# 2_RGB_s_knees.net
KiCad netlist of a schematic drawn in Altium Designer
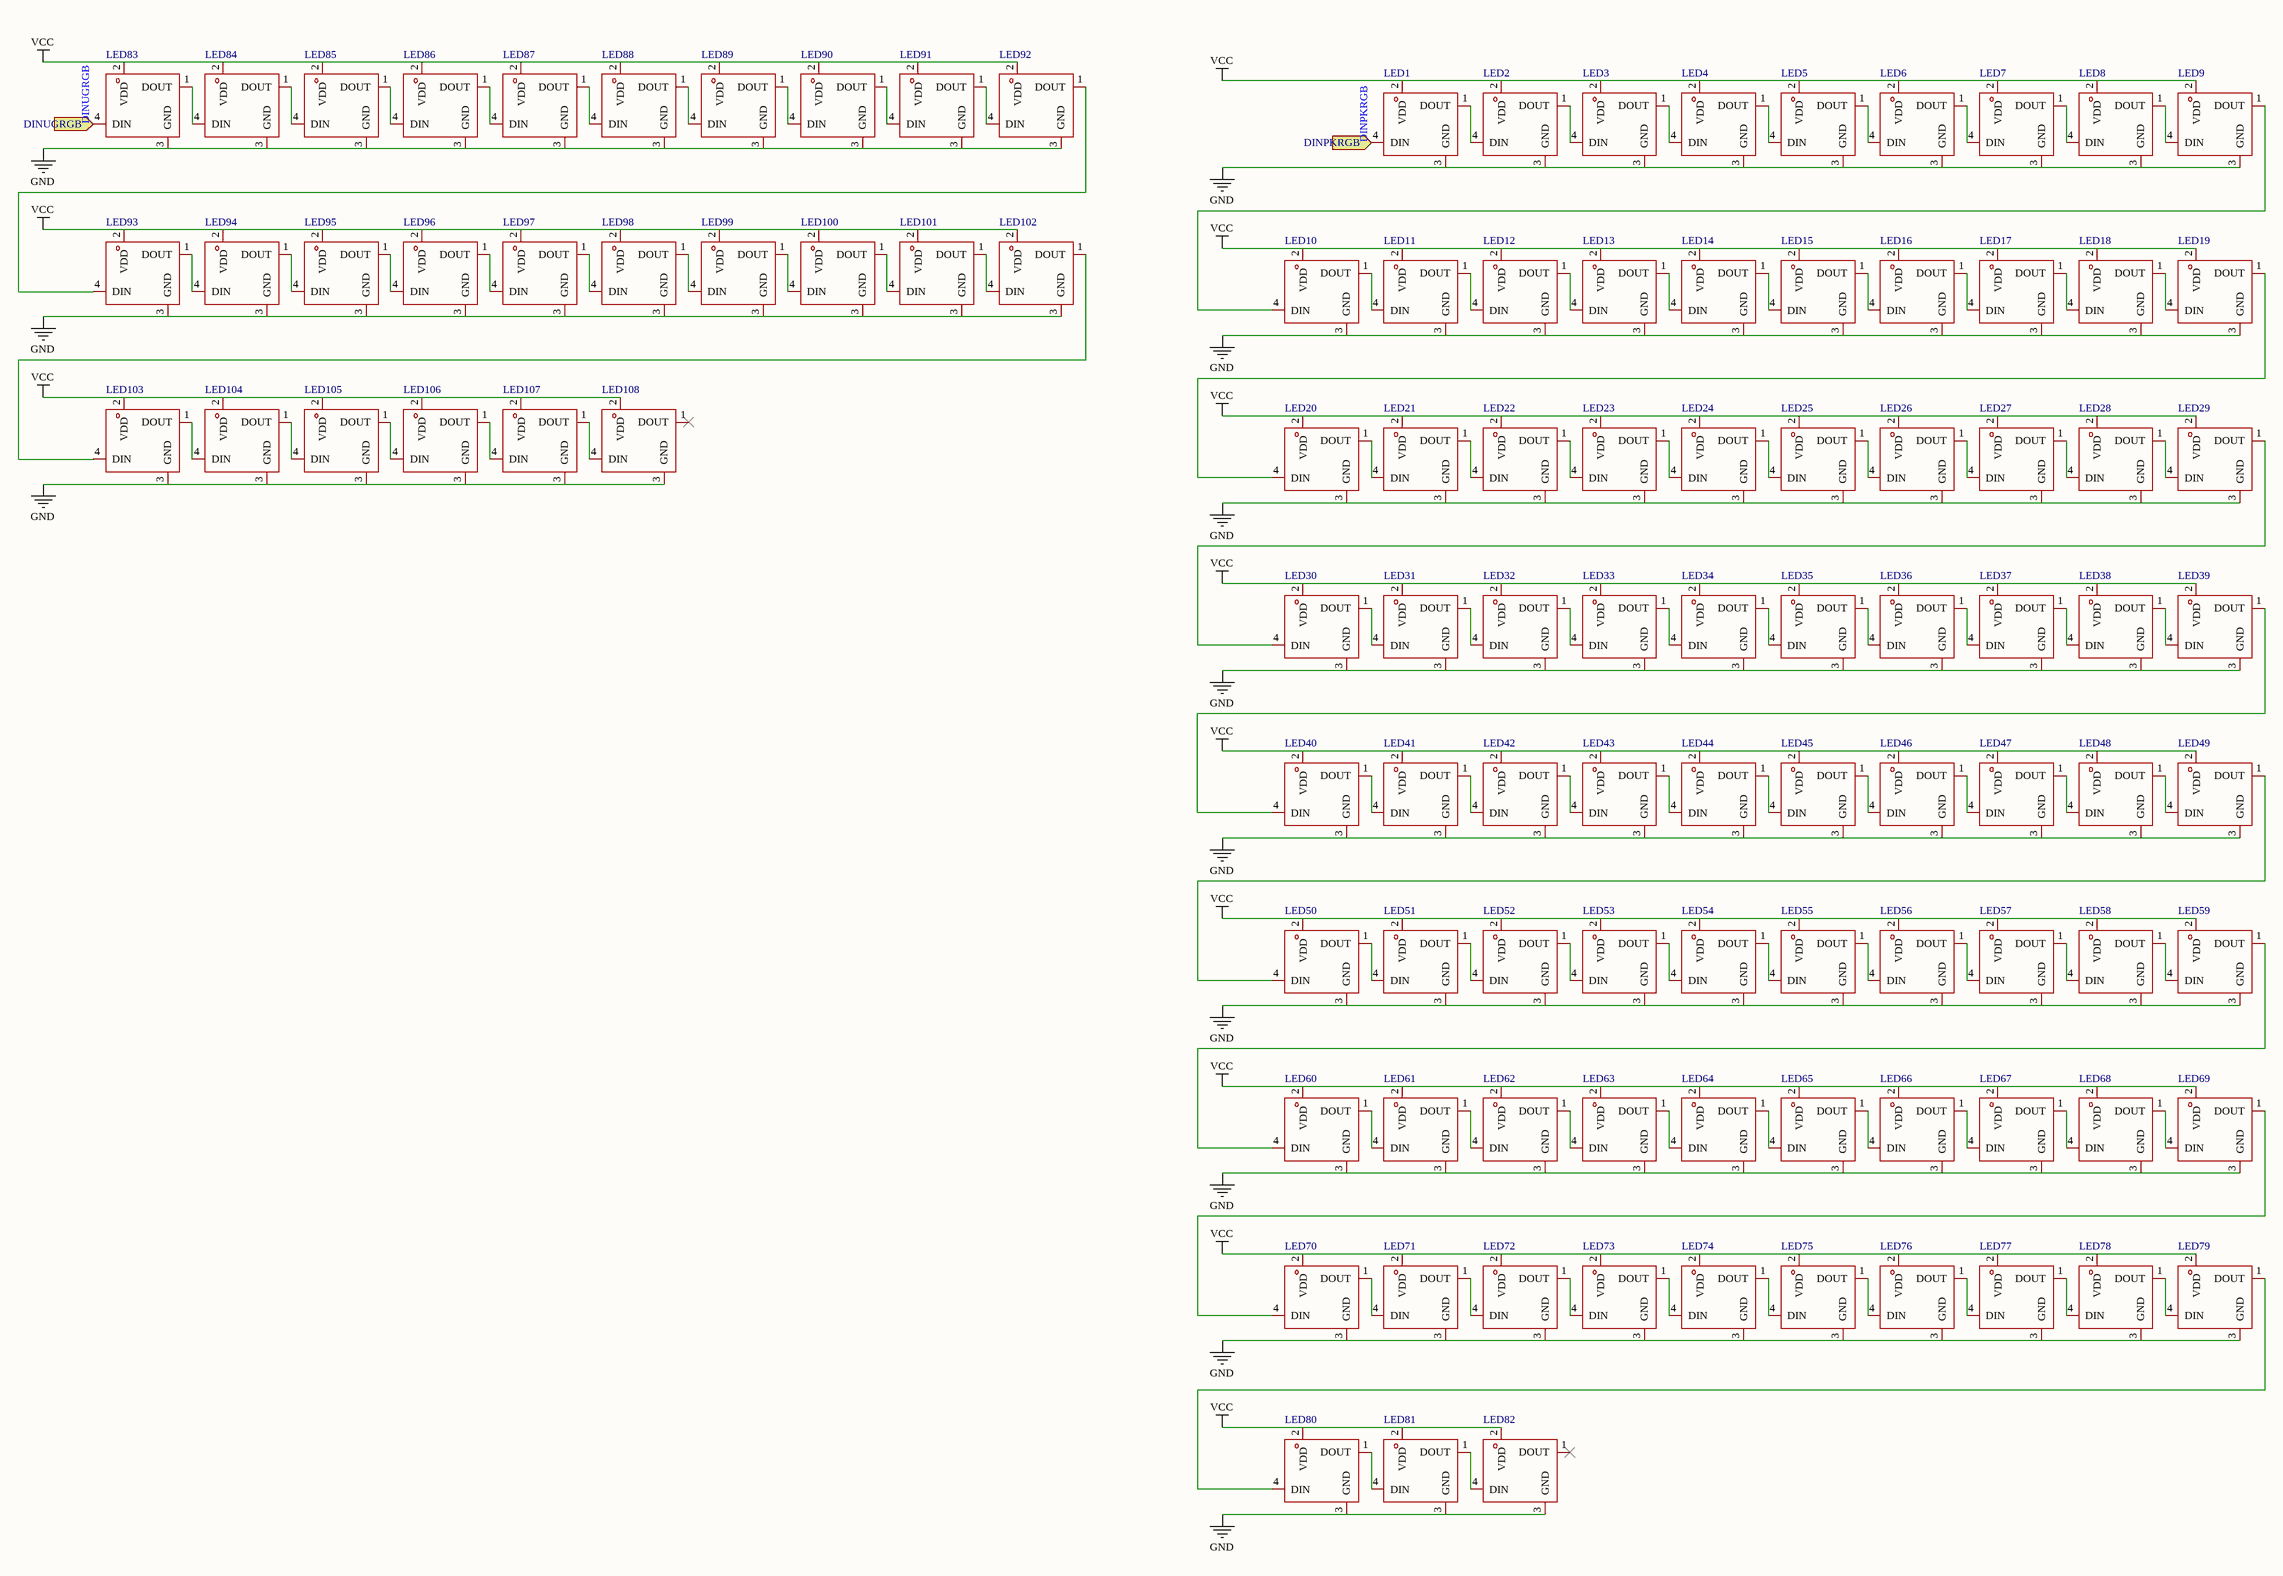
[diagram p0: 2_RGB's knees.schdoc]

(export (version "E")
  (design (tool "Eeschema 10.0.6"))
  (components
    (comp (ref "LED1")
      (value "XL-1010RGBC-WS2812B")
      (footprint "LED-SMD_4P-L1.0-W1.0-TL_XL-1010RGBC-WS2812B")
      (fields (field (name "MANUFACTURER") "XINGLIGHT(成兴光)"))
      (libsource (lib "altium-import") (part "root_0_XL-1010RGBC-WS2812B_"))
    )
    (comp (ref "LED2")
      (value "XL-1010RGBC-WS2812B")
      (footprint "LED-SMD_4P-L1.0-W1.0-TL_XL-1010RGBC-WS2812B")
      (fields (field (name "MANUFACTURER") "XINGLIGHT(成兴光)"))
      (libsource (lib "altium-import") (part "root_0_XL-1010RGBC-WS2812B_"))
    )
    (comp (ref "LED3")
      (value "XL-1010RGBC-WS2812B")
      (footprint "LED-SMD_4P-L1.0-W1.0-TL_XL-1010RGBC-WS2812B")
      (fields (field (name "MANUFACTURER") "XINGLIGHT(成兴光)"))
      (libsource (lib "altium-import") (part "root_0_XL-1010RGBC-WS2812B_"))
    )
    (comp (ref "LED4")
      (value "XL-1010RGBC-WS2812B")
      (footprint "LED-SMD_4P-L1.0-W1.0-TL_XL-1010RGBC-WS2812B")
      (fields (field (name "MANUFACTURER") "XINGLIGHT(成兴光)"))
      (libsource (lib "altium-import") (part "root_0_XL-1010RGBC-WS2812B_"))
    )
    (comp (ref "LED5")
      (value "XL-1010RGBC-WS2812B")
      (footprint "LED-SMD_4P-L1.0-W1.0-TL_XL-1010RGBC-WS2812B")
      (fields (field (name "MANUFACTURER") "XINGLIGHT(成兴光)"))
      (libsource (lib "altium-import") (part "root_0_XL-1010RGBC-WS2812B_"))
    )
    (comp (ref "LED6")
      (value "XL-1010RGBC-WS2812B")
      (footprint "LED-SMD_4P-L1.0-W1.0-TL_XL-1010RGBC-WS2812B")
      (fields (field (name "MANUFACTURER") "XINGLIGHT(成兴光)"))
      (libsource (lib "altium-import") (part "root_0_XL-1010RGBC-WS2812B_"))
    )
    (comp (ref "LED7")
      (value "XL-1010RGBC-WS2812B")
      (footprint "LED-SMD_4P-L1.0-W1.0-TL_XL-1010RGBC-WS2812B")
      (fields (field (name "MANUFACTURER") "XINGLIGHT(成兴光)"))
      (libsource (lib "altium-import") (part "root_0_XL-1010RGBC-WS2812B_"))
    )
    (comp (ref "LED8")
      (value "XL-1010RGBC-WS2812B")
      (footprint "LED-SMD_4P-L1.0-W1.0-TL_XL-1010RGBC-WS2812B")
      (fields (field (name "MANUFACTURER") "XINGLIGHT(成兴光)"))
      (libsource (lib "altium-import") (part "root_0_XL-1010RGBC-WS2812B_"))
    )
    (comp (ref "LED9")
      (value "XL-1010RGBC-WS2812B")
      (footprint "LED-SMD_4P-L1.0-W1.0-TL_XL-1010RGBC-WS2812B")
      (fields (field (name "MANUFACTURER") "XINGLIGHT(成兴光)"))
      (libsource (lib "altium-import") (part "root_0_XL-1010RGBC-WS2812B_"))
    )
    (comp (ref "LED10")
      (value "XL-1010RGBC-WS2812B")
      (footprint "LED-SMD_4P-L1.0-W1.0-TL_XL-1010RGBC-WS2812B")
      (fields (field (name "MANUFACTURER") "XINGLIGHT(成兴光)"))
      (libsource (lib "altium-import") (part "root_0_XL-1010RGBC-WS2812B_"))
    )
    (comp (ref "LED11")
      (value "XL-1010RGBC-WS2812B")
      (footprint "LED-SMD_4P-L1.0-W1.0-TL_XL-1010RGBC-WS2812B")
      (fields (field (name "MANUFACTURER") "XINGLIGHT(成兴光)"))
      (libsource (lib "altium-import") (part "root_0_XL-1010RGBC-WS2812B_"))
    )
    (comp (ref "LED12")
      (value "XL-1010RGBC-WS2812B")
      (footprint "LED-SMD_4P-L1.0-W1.0-TL_XL-1010RGBC-WS2812B")
      (fields (field (name "MANUFACTURER") "XINGLIGHT(成兴光)"))
      (libsource (lib "altium-import") (part "root_0_XL-1010RGBC-WS2812B_"))
    )
    (comp (ref "LED13")
      (value "XL-1010RGBC-WS2812B")
      (footprint "LED-SMD_4P-L1.0-W1.0-TL_XL-1010RGBC-WS2812B")
      (fields (field (name "MANUFACTURER") "XINGLIGHT(成兴光)"))
      (libsource (lib "altium-import") (part "root_0_XL-1010RGBC-WS2812B_"))
    )
    (comp (ref "LED14")
      (value "XL-1010RGBC-WS2812B")
      (footprint "LED-SMD_4P-L1.0-W1.0-TL_XL-1010RGBC-WS2812B")
      (fields (field (name "MANUFACTURER") "XINGLIGHT(成兴光)"))
      (libsource (lib "altium-import") (part "root_0_XL-1010RGBC-WS2812B_"))
    )
    (comp (ref "LED15")
      (value "XL-1010RGBC-WS2812B")
      (footprint "LED-SMD_4P-L1.0-W1.0-TL_XL-1010RGBC-WS2812B")
      (fields (field (name "MANUFACTURER") "XINGLIGHT(成兴光)"))
      (libsource (lib "altium-import") (part "root_0_XL-1010RGBC-WS2812B_"))
    )
    (comp (ref "LED16")
      (value "XL-1010RGBC-WS2812B")
      (footprint "LED-SMD_4P-L1.0-W1.0-TL_XL-1010RGBC-WS2812B")
      (fields (field (name "MANUFACTURER") "XINGLIGHT(成兴光)"))
      (libsource (lib "altium-import") (part "root_0_XL-1010RGBC-WS2812B_"))
    )
    (comp (ref "LED17")
      (value "XL-1010RGBC-WS2812B")
      (footprint "LED-SMD_4P-L1.0-W1.0-TL_XL-1010RGBC-WS2812B")
      (fields (field (name "MANUFACTURER") "XINGLIGHT(成兴光)"))
      (libsource (lib "altium-import") (part "root_0_XL-1010RGBC-WS2812B_"))
    )
    (comp (ref "LED18")
      (value "XL-1010RGBC-WS2812B")
      (footprint "LED-SMD_4P-L1.0-W1.0-TL_XL-1010RGBC-WS2812B")
      (fields (field (name "MANUFACTURER") "XINGLIGHT(成兴光)"))
      (libsource (lib "altium-import") (part "root_0_XL-1010RGBC-WS2812B_"))
    )
    (comp (ref "LED19")
      (value "XL-1010RGBC-WS2812B")
      (footprint "LED-SMD_4P-L1.0-W1.0-TL_XL-1010RGBC-WS2812B")
      (fields (field (name "MANUFACTURER") "XINGLIGHT(成兴光)"))
      (libsource (lib "altium-import") (part "root_0_XL-1010RGBC-WS2812B_"))
    )
    (comp (ref "LED20")
      (value "XL-1010RGBC-WS2812B")
      (footprint "LED-SMD_4P-L1.0-W1.0-TL_XL-1010RGBC-WS2812B")
      (fields (field (name "MANUFACTURER") "XINGLIGHT(成兴光)"))
      (libsource (lib "altium-import") (part "root_0_XL-1010RGBC-WS2812B_"))
    )
    (comp (ref "LED21")
      (value "XL-1010RGBC-WS2812B")
      (footprint "LED-SMD_4P-L1.0-W1.0-TL_XL-1010RGBC-WS2812B")
      (fields (field (name "MANUFACTURER") "XINGLIGHT(成兴光)"))
      (libsource (lib "altium-import") (part "root_0_XL-1010RGBC-WS2812B_"))
    )
    (comp (ref "LED22")
      (value "XL-1010RGBC-WS2812B")
      (footprint "LED-SMD_4P-L1.0-W1.0-TL_XL-1010RGBC-WS2812B")
      (fields (field (name "MANUFACTURER") "XINGLIGHT(成兴光)"))
      (libsource (lib "altium-import") (part "root_0_XL-1010RGBC-WS2812B_"))
    )
    (comp (ref "LED23")
      (value "XL-1010RGBC-WS2812B")
      (footprint "LED-SMD_4P-L1.0-W1.0-TL_XL-1010RGBC-WS2812B")
      (fields (field (name "MANUFACTURER") "XINGLIGHT(成兴光)"))
      (libsource (lib "altium-import") (part "root_0_XL-1010RGBC-WS2812B_"))
    )
    (comp (ref "LED24")
      (value "XL-1010RGBC-WS2812B")
      (footprint "LED-SMD_4P-L1.0-W1.0-TL_XL-1010RGBC-WS2812B")
      (fields (field (name "MANUFACTURER") "XINGLIGHT(成兴光)"))
      (libsource (lib "altium-import") (part "root_0_XL-1010RGBC-WS2812B_"))
    )
    (comp (ref "LED25")
      (value "XL-1010RGBC-WS2812B")
      (footprint "LED-SMD_4P-L1.0-W1.0-TL_XL-1010RGBC-WS2812B")
      (fields (field (name "MANUFACTURER") "XINGLIGHT(成兴光)"))
      (libsource (lib "altium-import") (part "root_0_XL-1010RGBC-WS2812B_"))
    )
    (comp (ref "LED26")
      (value "XL-1010RGBC-WS2812B")
      (footprint "LED-SMD_4P-L1.0-W1.0-TL_XL-1010RGBC-WS2812B")
      (fields (field (name "MANUFACTURER") "XINGLIGHT(成兴光)"))
      (libsource (lib "altium-import") (part "root_0_XL-1010RGBC-WS2812B_"))
    )
    (comp (ref "LED27")
      (value "XL-1010RGBC-WS2812B")
      (footprint "LED-SMD_4P-L1.0-W1.0-TL_XL-1010RGBC-WS2812B")
      (fields (field (name "MANUFACTURER") "XINGLIGHT(成兴光)"))
      (libsource (lib "altium-import") (part "root_0_XL-1010RGBC-WS2812B_"))
    )
    (comp (ref "LED28")
      (value "XL-1010RGBC-WS2812B")
      (footprint "LED-SMD_4P-L1.0-W1.0-TL_XL-1010RGBC-WS2812B")
      (fields (field (name "MANUFACTURER") "XINGLIGHT(成兴光)"))
      (libsource (lib "altium-import") (part "root_0_XL-1010RGBC-WS2812B_"))
    )
    (comp (ref "LED29")
      (value "XL-1010RGBC-WS2812B")
      (footprint "LED-SMD_4P-L1.0-W1.0-TL_XL-1010RGBC-WS2812B")
      (fields (field (name "MANUFACTURER") "XINGLIGHT(成兴光)"))
      (libsource (lib "altium-import") (part "root_0_XL-1010RGBC-WS2812B_"))
    )
    (comp (ref "LED30")
      (value "XL-1010RGBC-WS2812B")
      (footprint "LED-SMD_4P-L1.0-W1.0-TL_XL-1010RGBC-WS2812B")
      (fields (field (name "MANUFACTURER") "XINGLIGHT(成兴光)"))
      (libsource (lib "altium-import") (part "root_0_XL-1010RGBC-WS2812B_"))
    )
    (comp (ref "LED31")
      (value "XL-1010RGBC-WS2812B")
      (footprint "LED-SMD_4P-L1.0-W1.0-TL_XL-1010RGBC-WS2812B")
      (fields (field (name "MANUFACTURER") "XINGLIGHT(成兴光)"))
      (libsource (lib "altium-import") (part "root_0_XL-1010RGBC-WS2812B_"))
    )
    (comp (ref "LED32")
      (value "XL-1010RGBC-WS2812B")
      (footprint "LED-SMD_4P-L1.0-W1.0-TL_XL-1010RGBC-WS2812B")
      (fields (field (name "MANUFACTURER") "XINGLIGHT(成兴光)"))
      (libsource (lib "altium-import") (part "root_0_XL-1010RGBC-WS2812B_"))
    )
    (comp (ref "LED33")
      (value "XL-1010RGBC-WS2812B")
      (footprint "LED-SMD_4P-L1.0-W1.0-TL_XL-1010RGBC-WS2812B")
      (fields (field (name "MANUFACTURER") "XINGLIGHT(成兴光)"))
      (libsource (lib "altium-import") (part "root_0_XL-1010RGBC-WS2812B_"))
    )
    (comp (ref "LED34")
      (value "XL-1010RGBC-WS2812B")
      (footprint "LED-SMD_4P-L1.0-W1.0-TL_XL-1010RGBC-WS2812B")
      (fields (field (name "MANUFACTURER") "XINGLIGHT(成兴光)"))
      (libsource (lib "altium-import") (part "root_0_XL-1010RGBC-WS2812B_"))
    )
    (comp (ref "LED35")
      (value "XL-1010RGBC-WS2812B")
      (footprint "LED-SMD_4P-L1.0-W1.0-TL_XL-1010RGBC-WS2812B")
      (fields (field (name "MANUFACTURER") "XINGLIGHT(成兴光)"))
      (libsource (lib "altium-import") (part "root_0_XL-1010RGBC-WS2812B_"))
    )
    (comp (ref "LED36")
      (value "XL-1010RGBC-WS2812B")
      (footprint "LED-SMD_4P-L1.0-W1.0-TL_XL-1010RGBC-WS2812B")
      (fields (field (name "MANUFACTURER") "XINGLIGHT(成兴光)"))
      (libsource (lib "altium-import") (part "root_0_XL-1010RGBC-WS2812B_"))
    )
    (comp (ref "LED37")
      (value "XL-1010RGBC-WS2812B")
      (footprint "LED-SMD_4P-L1.0-W1.0-TL_XL-1010RGBC-WS2812B")
      (fields (field (name "MANUFACTURER") "XINGLIGHT(成兴光)"))
      (libsource (lib "altium-import") (part "root_0_XL-1010RGBC-WS2812B_"))
    )
    (comp (ref "LED38")
      (value "XL-1010RGBC-WS2812B")
      (footprint "LED-SMD_4P-L1.0-W1.0-TL_XL-1010RGBC-WS2812B")
      (fields (field (name "MANUFACTURER") "XINGLIGHT(成兴光)"))
      (libsource (lib "altium-import") (part "root_0_XL-1010RGBC-WS2812B_"))
    )
    (comp (ref "LED39")
      (value "XL-1010RGBC-WS2812B")
      (footprint "LED-SMD_4P-L1.0-W1.0-TL_XL-1010RGBC-WS2812B")
      (fields (field (name "MANUFACTURER") "XINGLIGHT(成兴光)"))
      (libsource (lib "altium-import") (part "root_0_XL-1010RGBC-WS2812B_"))
    )
    (comp (ref "LED40")
      (value "XL-1010RGBC-WS2812B")
      (footprint "LED-SMD_4P-L1.0-W1.0-TL_XL-1010RGBC-WS2812B")
      (fields (field (name "MANUFACTURER") "XINGLIGHT(成兴光)"))
      (libsource (lib "altium-import") (part "root_0_XL-1010RGBC-WS2812B_"))
    )
    (comp (ref "LED41")
      (value "XL-1010RGBC-WS2812B")
      (footprint "LED-SMD_4P-L1.0-W1.0-TL_XL-1010RGBC-WS2812B")
      (fields (field (name "MANUFACTURER") "XINGLIGHT(成兴光)"))
      (libsource (lib "altium-import") (part "root_0_XL-1010RGBC-WS2812B_"))
    )
    (comp (ref "LED42")
      (value "XL-1010RGBC-WS2812B")
      (footprint "LED-SMD_4P-L1.0-W1.0-TL_XL-1010RGBC-WS2812B")
      (fields (field (name "MANUFACTURER") "XINGLIGHT(成兴光)"))
      (libsource (lib "altium-import") (part "root_0_XL-1010RGBC-WS2812B_"))
    )
    (comp (ref "LED43")
      (value "XL-1010RGBC-WS2812B")
      (footprint "LED-SMD_4P-L1.0-W1.0-TL_XL-1010RGBC-WS2812B")
      (fields (field (name "MANUFACTURER") "XINGLIGHT(成兴光)"))
      (libsource (lib "altium-import") (part "root_0_XL-1010RGBC-WS2812B_"))
    )
    (comp (ref "LED44")
      (value "XL-1010RGBC-WS2812B")
      (footprint "LED-SMD_4P-L1.0-W1.0-TL_XL-1010RGBC-WS2812B")
      (fields (field (name "MANUFACTURER") "XINGLIGHT(成兴光)"))
      (libsource (lib "altium-import") (part "root_0_XL-1010RGBC-WS2812B_"))
    )
    (comp (ref "LED45")
      (value "XL-1010RGBC-WS2812B")
      (footprint "LED-SMD_4P-L1.0-W1.0-TL_XL-1010RGBC-WS2812B")
      (fields (field (name "MANUFACTURER") "XINGLIGHT(成兴光)"))
      (libsource (lib "altium-import") (part "root_0_XL-1010RGBC-WS2812B_"))
    )
    (comp (ref "LED46")
      (value "XL-1010RGBC-WS2812B")
      (footprint "LED-SMD_4P-L1.0-W1.0-TL_XL-1010RGBC-WS2812B")
      (fields (field (name "MANUFACTURER") "XINGLIGHT(成兴光)"))
      (libsource (lib "altium-import") (part "root_0_XL-1010RGBC-WS2812B_"))
    )
    (comp (ref "LED47")
      (value "XL-1010RGBC-WS2812B")
      (footprint "LED-SMD_4P-L1.0-W1.0-TL_XL-1010RGBC-WS2812B")
      (fields (field (name "MANUFACTURER") "XINGLIGHT(成兴光)"))
      (libsource (lib "altium-import") (part "root_0_XL-1010RGBC-WS2812B_"))
    )
    (comp (ref "LED48")
      (value "XL-1010RGBC-WS2812B")
      (footprint "LED-SMD_4P-L1.0-W1.0-TL_XL-1010RGBC-WS2812B")
      (fields (field (name "MANUFACTURER") "XINGLIGHT(成兴光)"))
      (libsource (lib "altium-import") (part "root_0_XL-1010RGBC-WS2812B_"))
    )
    (comp (ref "LED49")
      (value "XL-1010RGBC-WS2812B")
      (footprint "LED-SMD_4P-L1.0-W1.0-TL_XL-1010RGBC-WS2812B")
      (fields (field (name "MANUFACTURER") "XINGLIGHT(成兴光)"))
      (libsource (lib "altium-import") (part "root_0_XL-1010RGBC-WS2812B_"))
    )
    (comp (ref "LED50")
      (value "XL-1010RGBC-WS2812B")
      (footprint "LED-SMD_4P-L1.0-W1.0-TL_XL-1010RGBC-WS2812B")
      (fields (field (name "MANUFACTURER") "XINGLIGHT(成兴光)"))
      (libsource (lib "altium-import") (part "root_0_XL-1010RGBC-WS2812B_"))
    )
    (comp (ref "LED51")
      (value "XL-1010RGBC-WS2812B")
      (footprint "LED-SMD_4P-L1.0-W1.0-TL_XL-1010RGBC-WS2812B")
      (fields (field (name "MANUFACTURER") "XINGLIGHT(成兴光)"))
      (libsource (lib "altium-import") (part "root_0_XL-1010RGBC-WS2812B_"))
    )
    (comp (ref "LED52")
      (value "XL-1010RGBC-WS2812B")
      (footprint "LED-SMD_4P-L1.0-W1.0-TL_XL-1010RGBC-WS2812B")
      (fields (field (name "MANUFACTURER") "XINGLIGHT(成兴光)"))
      (libsource (lib "altium-import") (part "root_0_XL-1010RGBC-WS2812B_"))
    )
    (comp (ref "LED53")
      (value "XL-1010RGBC-WS2812B")
      (footprint "LED-SMD_4P-L1.0-W1.0-TL_XL-1010RGBC-WS2812B")
      (fields (field (name "MANUFACTURER") "XINGLIGHT(成兴光)"))
      (libsource (lib "altium-import") (part "root_0_XL-1010RGBC-WS2812B_"))
    )
    (comp (ref "LED54")
      (value "XL-1010RGBC-WS2812B")
      (footprint "LED-SMD_4P-L1.0-W1.0-TL_XL-1010RGBC-WS2812B")
      (fields (field (name "MANUFACTURER") "XINGLIGHT(成兴光)"))
      (libsource (lib "altium-import") (part "root_0_XL-1010RGBC-WS2812B_"))
    )
    (comp (ref "LED55")
      (value "XL-1010RGBC-WS2812B")
      (footprint "LED-SMD_4P-L1.0-W1.0-TL_XL-1010RGBC-WS2812B")
      (fields (field (name "MANUFACTURER") "XINGLIGHT(成兴光)"))
      (libsource (lib "altium-import") (part "root_0_XL-1010RGBC-WS2812B_"))
    )
    (comp (ref "LED56")
      (value "XL-1010RGBC-WS2812B")
      (footprint "LED-SMD_4P-L1.0-W1.0-TL_XL-1010RGBC-WS2812B")
      (fields (field (name "MANUFACTURER") "XINGLIGHT(成兴光)"))
      (libsource (lib "altium-import") (part "root_0_XL-1010RGBC-WS2812B_"))
    )
    (comp (ref "LED57")
      (value "XL-1010RGBC-WS2812B")
      (footprint "LED-SMD_4P-L1.0-W1.0-TL_XL-1010RGBC-WS2812B")
      (fields (field (name "MANUFACTURER") "XINGLIGHT(成兴光)"))
      (libsource (lib "altium-import") (part "root_0_XL-1010RGBC-WS2812B_"))
    )
    (comp (ref "LED58")
      (value "XL-1010RGBC-WS2812B")
      (footprint "LED-SMD_4P-L1.0-W1.0-TL_XL-1010RGBC-WS2812B")
      (fields (field (name "MANUFACTURER") "XINGLIGHT(成兴光)"))
      (libsource (lib "altium-import") (part "root_0_XL-1010RGBC-WS2812B_"))
    )
    (comp (ref "LED59")
      (value "XL-1010RGBC-WS2812B")
      (footprint "LED-SMD_4P-L1.0-W1.0-TL_XL-1010RGBC-WS2812B")
      (fields (field (name "MANUFACTURER") "XINGLIGHT(成兴光)"))
      (libsource (lib "altium-import") (part "root_0_XL-1010RGBC-WS2812B_"))
    )
    (comp (ref "LED60")
      (value "XL-1010RGBC-WS2812B")
      (footprint "LED-SMD_4P-L1.0-W1.0-TL_XL-1010RGBC-WS2812B")
      (fields (field (name "MANUFACTURER") "XINGLIGHT(成兴光)"))
      (libsource (lib "altium-import") (part "root_0_XL-1010RGBC-WS2812B_"))
    )
    (comp (ref "LED61")
      (value "XL-1010RGBC-WS2812B")
      (footprint "LED-SMD_4P-L1.0-W1.0-TL_XL-1010RGBC-WS2812B")
      (fields (field (name "MANUFACTURER") "XINGLIGHT(成兴光)"))
      (libsource (lib "altium-import") (part "root_0_XL-1010RGBC-WS2812B_"))
    )
    (comp (ref "LED62")
      (value "XL-1010RGBC-WS2812B")
      (footprint "LED-SMD_4P-L1.0-W1.0-TL_XL-1010RGBC-WS2812B")
      (fields (field (name "MANUFACTURER") "XINGLIGHT(成兴光)"))
      (libsource (lib "altium-import") (part "root_0_XL-1010RGBC-WS2812B_"))
    )
    (comp (ref "LED63")
      (value "XL-1010RGBC-WS2812B")
      (footprint "LED-SMD_4P-L1.0-W1.0-TL_XL-1010RGBC-WS2812B")
      (fields (field (name "MANUFACTURER") "XINGLIGHT(成兴光)"))
      (libsource (lib "altium-import") (part "root_0_XL-1010RGBC-WS2812B_"))
    )
    (comp (ref "LED64")
      (value "XL-1010RGBC-WS2812B")
      (footprint "LED-SMD_4P-L1.0-W1.0-TL_XL-1010RGBC-WS2812B")
      (fields (field (name "MANUFACTURER") "XINGLIGHT(成兴光)"))
      (libsource (lib "altium-import") (part "root_0_XL-1010RGBC-WS2812B_"))
    )
    (comp (ref "LED65")
      (value "XL-1010RGBC-WS2812B")
      (footprint "LED-SMD_4P-L1.0-W1.0-TL_XL-1010RGBC-WS2812B")
      (fields (field (name "MANUFACTURER") "XINGLIGHT(成兴光)"))
      (libsource (lib "altium-import") (part "root_0_XL-1010RGBC-WS2812B_"))
    )
    (comp (ref "LED66")
      (value "XL-1010RGBC-WS2812B")
      (footprint "LED-SMD_4P-L1.0-W1.0-TL_XL-1010RGBC-WS2812B")
      (fields (field (name "MANUFACTURER") "XINGLIGHT(成兴光)"))
      (libsource (lib "altium-import") (part "root_0_XL-1010RGBC-WS2812B_"))
    )
    (comp (ref "LED67")
      (value "XL-1010RGBC-WS2812B")
      (footprint "LED-SMD_4P-L1.0-W1.0-TL_XL-1010RGBC-WS2812B")
      (fields (field (name "MANUFACTURER") "XINGLIGHT(成兴光)"))
      (libsource (lib "altium-import") (part "root_0_XL-1010RGBC-WS2812B_"))
    )
    (comp (ref "LED68")
      (value "XL-1010RGBC-WS2812B")
      (footprint "LED-SMD_4P-L1.0-W1.0-TL_XL-1010RGBC-WS2812B")
      (fields (field (name "MANUFACTURER") "XINGLIGHT(成兴光)"))
      (libsource (lib "altium-import") (part "root_0_XL-1010RGBC-WS2812B_"))
    )
    (comp (ref "LED69")
      (value "XL-1010RGBC-WS2812B")
      (footprint "LED-SMD_4P-L1.0-W1.0-TL_XL-1010RGBC-WS2812B")
      (fields (field (name "MANUFACTURER") "XINGLIGHT(成兴光)"))
      (libsource (lib "altium-import") (part "root_0_XL-1010RGBC-WS2812B_"))
    )
    (comp (ref "LED70")
      (value "XL-1010RGBC-WS2812B")
      (footprint "LED-SMD_4P-L1.0-W1.0-TL_XL-1010RGBC-WS2812B")
      (fields (field (name "MANUFACTURER") "XINGLIGHT(成兴光)"))
      (libsource (lib "altium-import") (part "root_0_XL-1010RGBC-WS2812B_"))
    )
    (comp (ref "LED71")
      (value "XL-1010RGBC-WS2812B")
      (footprint "LED-SMD_4P-L1.0-W1.0-TL_XL-1010RGBC-WS2812B")
      (fields (field (name "MANUFACTURER") "XINGLIGHT(成兴光)"))
      (libsource (lib "altium-import") (part "root_0_XL-1010RGBC-WS2812B_"))
    )
    (comp (ref "LED72")
      (value "XL-1010RGBC-WS2812B")
      (footprint "LED-SMD_4P-L1.0-W1.0-TL_XL-1010RGBC-WS2812B")
      (fields (field (name "MANUFACTURER") "XINGLIGHT(成兴光)"))
      (libsource (lib "altium-import") (part "root_0_XL-1010RGBC-WS2812B_"))
    )
    (comp (ref "LED73")
      (value "XL-1010RGBC-WS2812B")
      (footprint "LED-SMD_4P-L1.0-W1.0-TL_XL-1010RGBC-WS2812B")
      (fields (field (name "MANUFACTURER") "XINGLIGHT(成兴光)"))
      (libsource (lib "altium-import") (part "root_0_XL-1010RGBC-WS2812B_"))
    )
    (comp (ref "LED74")
      (value "XL-1010RGBC-WS2812B")
      (footprint "LED-SMD_4P-L1.0-W1.0-TL_XL-1010RGBC-WS2812B")
      (fields (field (name "MANUFACTURER") "XINGLIGHT(成兴光)"))
      (libsource (lib "altium-import") (part "root_0_XL-1010RGBC-WS2812B_"))
    )
    (comp (ref "LED75")
      (value "XL-1010RGBC-WS2812B")
      (footprint "LED-SMD_4P-L1.0-W1.0-TL_XL-1010RGBC-WS2812B")
      (fields (field (name "MANUFACTURER") "XINGLIGHT(成兴光)"))
      (libsource (lib "altium-import") (part "root_0_XL-1010RGBC-WS2812B_"))
    )
    (comp (ref "LED76")
      (value "XL-1010RGBC-WS2812B")
      (footprint "LED-SMD_4P-L1.0-W1.0-TL_XL-1010RGBC-WS2812B")
      (fields (field (name "MANUFACTURER") "XINGLIGHT(成兴光)"))
      (libsource (lib "altium-import") (part "root_0_XL-1010RGBC-WS2812B_"))
    )
    (comp (ref "LED77")
      (value "XL-1010RGBC-WS2812B")
      (footprint "LED-SMD_4P-L1.0-W1.0-TL_XL-1010RGBC-WS2812B")
      (fields (field (name "MANUFACTURER") "XINGLIGHT(成兴光)"))
      (libsource (lib "altium-import") (part "root_0_XL-1010RGBC-WS2812B_"))
    )
    (comp (ref "LED78")
      (value "XL-1010RGBC-WS2812B")
      (footprint "LED-SMD_4P-L1.0-W1.0-TL_XL-1010RGBC-WS2812B")
      (fields (field (name "MANUFACTURER") "XINGLIGHT(成兴光)"))
      (libsource (lib "altium-import") (part "root_0_XL-1010RGBC-WS2812B_"))
    )
    (comp (ref "LED79")
      (value "XL-1010RGBC-WS2812B")
      (footprint "LED-SMD_4P-L1.0-W1.0-TL_XL-1010RGBC-WS2812B")
      (fields (field (name "MANUFACTURER") "XINGLIGHT(成兴光)"))
      (libsource (lib "altium-import") (part "root_0_XL-1010RGBC-WS2812B_"))
    )
    (comp (ref "LED80")
      (value "XL-1010RGBC-WS2812B")
      (footprint "LED-SMD_4P-L1.0-W1.0-TL_XL-1010RGBC-WS2812B")
      (fields (field (name "MANUFACTURER") "XINGLIGHT(成兴光)"))
      (libsource (lib "altium-import") (part "root_0_XL-1010RGBC-WS2812B_"))
    )
    (comp (ref "LED81")
      (value "XL-1010RGBC-WS2812B")
      (footprint "LED-SMD_4P-L1.0-W1.0-TL_XL-1010RGBC-WS2812B")
      (fields (field (name "MANUFACTURER") "XINGLIGHT(成兴光)"))
      (libsource (lib "altium-import") (part "root_0_XL-1010RGBC-WS2812B_"))
    )
    (comp (ref "LED82")
      (value "XL-1010RGBC-WS2812B")
      (footprint "LED-SMD_4P-L1.0-W1.0-TL_XL-1010RGBC-WS2812B")
      (fields (field (name "MANUFACTURER") "XINGLIGHT(成兴光)"))
      (libsource (lib "altium-import") (part "root_0_XL-1010RGBC-WS2812B_"))
    )
    (comp (ref "LED83")
      (value "XL-1010RGBC-WS2812B")
      (footprint "LED-SMD_4P-L1.0-W1.0-TL_XL-1010RGBC-WS2812B")
      (fields (field (name "MANUFACTURER") "XINGLIGHT(成兴光)"))
      (libsource (lib "altium-import") (part "root_0_XL-1010RGBC-WS2812B_"))
    )
    (comp (ref "LED84")
      (value "XL-1010RGBC-WS2812B")
      (footprint "LED-SMD_4P-L1.0-W1.0-TL_XL-1010RGBC-WS2812B")
      (fields (field (name "MANUFACTURER") "XINGLIGHT(成兴光)"))
      (libsource (lib "altium-import") (part "root_0_XL-1010RGBC-WS2812B_"))
    )
    (comp (ref "LED85")
      (value "XL-1010RGBC-WS2812B")
      (footprint "LED-SMD_4P-L1.0-W1.0-TL_XL-1010RGBC-WS2812B")
      (fields (field (name "MANUFACTURER") "XINGLIGHT(成兴光)"))
      (libsource (lib "altium-import") (part "root_0_XL-1010RGBC-WS2812B_"))
    )
    (comp (ref "LED86")
      (value "XL-1010RGBC-WS2812B")
      (footprint "LED-SMD_4P-L1.0-W1.0-TL_XL-1010RGBC-WS2812B")
      (fields (field (name "MANUFACTURER") "XINGLIGHT(成兴光)"))
      (libsource (lib "altium-import") (part "root_0_XL-1010RGBC-WS2812B_"))
    )
    (comp (ref "LED87")
      (value "XL-1010RGBC-WS2812B")
      (footprint "LED-SMD_4P-L1.0-W1.0-TL_XL-1010RGBC-WS2812B")
      (fields (field (name "MANUFACTURER") "XINGLIGHT(成兴光)"))
      (libsource (lib "altium-import") (part "root_0_XL-1010RGBC-WS2812B_"))
    )
    (comp (ref "LED88")
      (value "XL-1010RGBC-WS2812B")
      (footprint "LED-SMD_4P-L1.0-W1.0-TL_XL-1010RGBC-WS2812B")
      (fields (field (name "MANUFACTURER") "XINGLIGHT(成兴光)"))
      (libsource (lib "altium-import") (part "root_0_XL-1010RGBC-WS2812B_"))
    )
    (comp (ref "LED89")
      (value "XL-1010RGBC-WS2812B")
      (footprint "LED-SMD_4P-L1.0-W1.0-TL_XL-1010RGBC-WS2812B")
      (fields (field (name "MANUFACTURER") "XINGLIGHT(成兴光)"))
      (libsource (lib "altium-import") (part "root_0_XL-1010RGBC-WS2812B_"))
    )
    (comp (ref "LED90")
      (value "XL-1010RGBC-WS2812B")
      (footprint "LED-SMD_4P-L1.0-W1.0-TL_XL-1010RGBC-WS2812B")
      (fields (field (name "MANUFACTURER") "XINGLIGHT(成兴光)"))
      (libsource (lib "altium-import") (part "root_0_XL-1010RGBC-WS2812B_"))
    )
    (comp (ref "LED91")
      (value "XL-1010RGBC-WS2812B")
      (footprint "LED-SMD_4P-L1.0-W1.0-TL_XL-1010RGBC-WS2812B")
      (fields (field (name "MANUFACTURER") "XINGLIGHT(成兴光)"))
      (libsource (lib "altium-import") (part "root_0_XL-1010RGBC-WS2812B_"))
    )
    (comp (ref "LED92")
      (value "XL-1010RGBC-WS2812B")
      (footprint "LED-SMD_4P-L1.0-W1.0-TL_XL-1010RGBC-WS2812B")
      (fields (field (name "MANUFACTURER") "XINGLIGHT(成兴光)"))
      (libsource (lib "altium-import") (part "root_0_XL-1010RGBC-WS2812B_"))
    )
    (comp (ref "LED93")
      (value "XL-1010RGBC-WS2812B")
      (footprint "LED-SMD_4P-L1.0-W1.0-TL_XL-1010RGBC-WS2812B")
      (fields (field (name "MANUFACTURER") "XINGLIGHT(成兴光)"))
      (libsource (lib "altium-import") (part "root_0_XL-1010RGBC-WS2812B_"))
    )
    (comp (ref "LED94")
      (value "XL-1010RGBC-WS2812B")
      (footprint "LED-SMD_4P-L1.0-W1.0-TL_XL-1010RGBC-WS2812B")
      (fields (field (name "MANUFACTURER") "XINGLIGHT(成兴光)"))
      (libsource (lib "altium-import") (part "root_0_XL-1010RGBC-WS2812B_"))
    )
    (comp (ref "LED95")
      (value "XL-1010RGBC-WS2812B")
      (footprint "LED-SMD_4P-L1.0-W1.0-TL_XL-1010RGBC-WS2812B")
      (fields (field (name "MANUFACTURER") "XINGLIGHT(成兴光)"))
      (libsource (lib "altium-import") (part "root_0_XL-1010RGBC-WS2812B_"))
    )
    (comp (ref "LED96")
      (value "XL-1010RGBC-WS2812B")
      (footprint "LED-SMD_4P-L1.0-W1.0-TL_XL-1010RGBC-WS2812B")
      (fields (field (name "MANUFACTURER") "XINGLIGHT(成兴光)"))
      (libsource (lib "altium-import") (part "root_0_XL-1010RGBC-WS2812B_"))
    )
    (comp (ref "LED97")
      (value "XL-1010RGBC-WS2812B")
      (footprint "LED-SMD_4P-L1.0-W1.0-TL_XL-1010RGBC-WS2812B")
      (fields (field (name "MANUFACTURER") "XINGLIGHT(成兴光)"))
      (libsource (lib "altium-import") (part "root_0_XL-1010RGBC-WS2812B_"))
    )
    (comp (ref "LED98")
      (value "XL-1010RGBC-WS2812B")
      (footprint "LED-SMD_4P-L1.0-W1.0-TL_XL-1010RGBC-WS2812B")
      (fields (field (name "MANUFACTURER") "XINGLIGHT(成兴光)"))
      (libsource (lib "altium-import") (part "root_0_XL-1010RGBC-WS2812B_"))
    )
    (comp (ref "LED99")
      (value "XL-1010RGBC-WS2812B")
      (footprint "LED-SMD_4P-L1.0-W1.0-TL_XL-1010RGBC-WS2812B")
      (fields (field (name "MANUFACTURER") "XINGLIGHT(成兴光)"))
      (libsource (lib "altium-import") (part "root_0_XL-1010RGBC-WS2812B_"))
    )
    (comp (ref "LED100")
      (value "XL-1010RGBC-WS2812B")
      (footprint "LED-SMD_4P-L1.0-W1.0-TL_XL-1010RGBC-WS2812B")
      (fields (field (name "MANUFACTURER") "XINGLIGHT(成兴光)"))
      (libsource (lib "altium-import") (part "root_0_XL-1010RGBC-WS2812B_"))
    )
    (comp (ref "LED101")
      (value "XL-1010RGBC-WS2812B")
      (footprint "LED-SMD_4P-L1.0-W1.0-TL_XL-1010RGBC-WS2812B")
      (fields (field (name "MANUFACTURER") "XINGLIGHT(成兴光)"))
      (libsource (lib "altium-import") (part "root_0_XL-1010RGBC-WS2812B_"))
    )
    (comp (ref "LED102")
      (value "XL-1010RGBC-WS2812B")
      (footprint "LED-SMD_4P-L1.0-W1.0-TL_XL-1010RGBC-WS2812B")
      (fields (field (name "MANUFACTURER") "XINGLIGHT(成兴光)"))
      (libsource (lib "altium-import") (part "root_0_XL-1010RGBC-WS2812B_"))
    )
    (comp (ref "LED103")
      (value "XL-1010RGBC-WS2812B")
      (footprint "LED-SMD_4P-L1.0-W1.0-TL_XL-1010RGBC-WS2812B")
      (fields (field (name "MANUFACTURER") "XINGLIGHT(成兴光)"))
      (libsource (lib "altium-import") (part "root_0_XL-1010RGBC-WS2812B_"))
    )
    (comp (ref "LED104")
      (value "XL-1010RGBC-WS2812B")
      (footprint "LED-SMD_4P-L1.0-W1.0-TL_XL-1010RGBC-WS2812B")
      (fields (field (name "MANUFACTURER") "XINGLIGHT(成兴光)"))
      (libsource (lib "altium-import") (part "root_0_XL-1010RGBC-WS2812B_"))
    )
    (comp (ref "LED105")
      (value "XL-1010RGBC-WS2812B")
      (footprint "LED-SMD_4P-L1.0-W1.0-TL_XL-1010RGBC-WS2812B")
      (fields (field (name "MANUFACTURER") "XINGLIGHT(成兴光)"))
      (libsource (lib "altium-import") (part "root_0_XL-1010RGBC-WS2812B_"))
    )
    (comp (ref "LED106")
      (value "XL-1010RGBC-WS2812B")
      (footprint "LED-SMD_4P-L1.0-W1.0-TL_XL-1010RGBC-WS2812B")
      (fields (field (name "MANUFACTURER") "XINGLIGHT(成兴光)"))
      (libsource (lib "altium-import") (part "root_0_XL-1010RGBC-WS2812B_"))
    )
    (comp (ref "LED107")
      (value "XL-1010RGBC-WS2812B")
      (footprint "LED-SMD_4P-L1.0-W1.0-TL_XL-1010RGBC-WS2812B")
      (fields (field (name "MANUFACTURER") "XINGLIGHT(成兴光)"))
      (libsource (lib "altium-import") (part "root_0_XL-1010RGBC-WS2812B_"))
    )
    (comp (ref "LED108")
      (value "XL-1010RGBC-WS2812B")
      (footprint "LED-SMD_4P-L1.0-W1.0-TL_XL-1010RGBC-WS2812B")
      (fields (field (name "MANUFACTURER") "XINGLIGHT(成兴光)"))
      (libsource (lib "altium-import") (part "root_0_XL-1010RGBC-WS2812B_"))
    )
  )
  (nets
    (net (code "1") (name "/DINPKRGB") (class "Default")
      (node (ref "LED1") (pin "4") (pinfunction "DIN_4") (pintype "passive"))
    )
    (net (code "2") (name "/DINUGRGB") (class "Default")
      (node (ref "LED83") (pin "4") (pinfunction "DIN_4") (pintype "passive"))
    )
    (net (code "3") (name "GND") (class "Default")
      (node (ref "LED1") (pin "3") (pinfunction "GND_3") (pintype "passive"))
      (node (ref "LED10") (pin "3") (pinfunction "GND_3") (pintype "passive"))
      (node (ref "LED100") (pin "3") (pinfunction "GND_3") (pintype "passive"))
      (node (ref "LED101") (pin "3") (pinfunction "GND_3") (pintype "passive"))
      (node (ref "LED102") (pin "3") (pinfunction "GND_3") (pintype "passive"))
      (node (ref "LED103") (pin "3") (pinfunction "GND_3") (pintype "passive"))
      (node (ref "LED104") (pin "3") (pinfunction "GND_3") (pintype "passive"))
      (node (ref "LED105") (pin "3") (pinfunction "GND_3") (pintype "passive"))
      (node (ref "LED106") (pin "3") (pinfunction "GND_3") (pintype "passive"))
      (node (ref "LED107") (pin "3") (pinfunction "GND_3") (pintype "passive"))
      (node (ref "LED108") (pin "3") (pinfunction "GND_3") (pintype "passive"))
      (node (ref "LED11") (pin "3") (pinfunction "GND_3") (pintype "passive"))
      (node (ref "LED12") (pin "3") (pinfunction "GND_3") (pintype "passive"))
      (node (ref "LED13") (pin "3") (pinfunction "GND_3") (pintype "passive"))
      (node (ref "LED14") (pin "3") (pinfunction "GND_3") (pintype "passive"))
      (node (ref "LED15") (pin "3") (pinfunction "GND_3") (pintype "passive"))
      (node (ref "LED16") (pin "3") (pinfunction "GND_3") (pintype "passive"))
      (node (ref "LED17") (pin "3") (pinfunction "GND_3") (pintype "passive"))
      (node (ref "LED18") (pin "3") (pinfunction "GND_3") (pintype "passive"))
      (node (ref "LED19") (pin "3") (pinfunction "GND_3") (pintype "passive"))
      (node (ref "LED2") (pin "3") (pinfunction "GND_3") (pintype "passive"))
      (node (ref "LED20") (pin "3") (pinfunction "GND_3") (pintype "passive"))
      (node (ref "LED21") (pin "3") (pinfunction "GND_3") (pintype "passive"))
      (node (ref "LED22") (pin "3") (pinfunction "GND_3") (pintype "passive"))
      (node (ref "LED23") (pin "3") (pinfunction "GND_3") (pintype "passive"))
      (node (ref "LED24") (pin "3") (pinfunction "GND_3") (pintype "passive"))
      (node (ref "LED25") (pin "3") (pinfunction "GND_3") (pintype "passive"))
      (node (ref "LED26") (pin "3") (pinfunction "GND_3") (pintype "passive"))
      (node (ref "LED27") (pin "3") (pinfunction "GND_3") (pintype "passive"))
      (node (ref "LED28") (pin "3") (pinfunction "GND_3") (pintype "passive"))
      (node (ref "LED29") (pin "3") (pinfunction "GND_3") (pintype "passive"))
      (node (ref "LED3") (pin "3") (pinfunction "GND_3") (pintype "passive"))
      (node (ref "LED30") (pin "3") (pinfunction "GND_3") (pintype "passive"))
      (node (ref "LED31") (pin "3") (pinfunction "GND_3") (pintype "passive"))
      (node (ref "LED32") (pin "3") (pinfunction "GND_3") (pintype "passive"))
      (node (ref "LED33") (pin "3") (pinfunction "GND_3") (pintype "passive"))
      (node (ref "LED34") (pin "3") (pinfunction "GND_3") (pintype "passive"))
      (node (ref "LED35") (pin "3") (pinfunction "GND_3") (pintype "passive"))
      (node (ref "LED36") (pin "3") (pinfunction "GND_3") (pintype "passive"))
      (node (ref "LED37") (pin "3") (pinfunction "GND_3") (pintype "passive"))
      (node (ref "LED38") (pin "3") (pinfunction "GND_3") (pintype "passive"))
      (node (ref "LED39") (pin "3") (pinfunction "GND_3") (pintype "passive"))
      (node (ref "LED4") (pin "3") (pinfunction "GND_3") (pintype "passive"))
      (node (ref "LED40") (pin "3") (pinfunction "GND_3") (pintype "passive"))
      (node (ref "LED41") (pin "3") (pinfunction "GND_3") (pintype "passive"))
      (node (ref "LED42") (pin "3") (pinfunction "GND_3") (pintype "passive"))
      (node (ref "LED43") (pin "3") (pinfunction "GND_3") (pintype "passive"))
      (node (ref "LED44") (pin "3") (pinfunction "GND_3") (pintype "passive"))
      (node (ref "LED45") (pin "3") (pinfunction "GND_3") (pintype "passive"))
      (node (ref "LED46") (pin "3") (pinfunction "GND_3") (pintype "passive"))
      (node (ref "LED47") (pin "3") (pinfunction "GND_3") (pintype "passive"))
      (node (ref "LED48") (pin "3") (pinfunction "GND_3") (pintype "passive"))
      (node (ref "LED49") (pin "3") (pinfunction "GND_3") (pintype "passive"))
      (node (ref "LED5") (pin "3") (pinfunction "GND_3") (pintype "passive"))
      (node (ref "LED50") (pin "3") (pinfunction "GND_3") (pintype "passive"))
      (node (ref "LED51") (pin "3") (pinfunction "GND_3") (pintype "passive"))
      (node (ref "LED52") (pin "3") (pinfunction "GND_3") (pintype "passive"))
      (node (ref "LED53") (pin "3") (pinfunction "GND_3") (pintype "passive"))
      (node (ref "LED54") (pin "3") (pinfunction "GND_3") (pintype "passive"))
      (node (ref "LED55") (pin "3") (pinfunction "GND_3") (pintype "passive"))
      (node (ref "LED56") (pin "3") (pinfunction "GND_3") (pintype "passive"))
      (node (ref "LED57") (pin "3") (pinfunction "GND_3") (pintype "passive"))
      (node (ref "LED58") (pin "3") (pinfunction "GND_3") (pintype "passive"))
      (node (ref "LED59") (pin "3") (pinfunction "GND_3") (pintype "passive"))
      (node (ref "LED6") (pin "3") (pinfunction "GND_3") (pintype "passive"))
      (node (ref "LED60") (pin "3") (pinfunction "GND_3") (pintype "passive"))
      (node (ref "LED61") (pin "3") (pinfunction "GND_3") (pintype "passive"))
      (node (ref "LED62") (pin "3") (pinfunction "GND_3") (pintype "passive"))
      (node (ref "LED63") (pin "3") (pinfunction "GND_3") (pintype "passive"))
      (node (ref "LED64") (pin "3") (pinfunction "GND_3") (pintype "passive"))
      (node (ref "LED65") (pin "3") (pinfunction "GND_3") (pintype "passive"))
      (node (ref "LED66") (pin "3") (pinfunction "GND_3") (pintype "passive"))
      (node (ref "LED67") (pin "3") (pinfunction "GND_3") (pintype "passive"))
      (node (ref "LED68") (pin "3") (pinfunction "GND_3") (pintype "passive"))
      (node (ref "LED69") (pin "3") (pinfunction "GND_3") (pintype "passive"))
      (node (ref "LED7") (pin "3") (pinfunction "GND_3") (pintype "passive"))
      (node (ref "LED70") (pin "3") (pinfunction "GND_3") (pintype "passive"))
      (node (ref "LED71") (pin "3") (pinfunction "GND_3") (pintype "passive"))
      (node (ref "LED72") (pin "3") (pinfunction "GND_3") (pintype "passive"))
      (node (ref "LED73") (pin "3") (pinfunction "GND_3") (pintype "passive"))
      (node (ref "LED74") (pin "3") (pinfunction "GND_3") (pintype "passive"))
      (node (ref "LED75") (pin "3") (pinfunction "GND_3") (pintype "passive"))
      (node (ref "LED76") (pin "3") (pinfunction "GND_3") (pintype "passive"))
      (node (ref "LED77") (pin "3") (pinfunction "GND_3") (pintype "passive"))
      (node (ref "LED78") (pin "3") (pinfunction "GND_3") (pintype "passive"))
      (node (ref "LED79") (pin "3") (pinfunction "GND_3") (pintype "passive"))
      (node (ref "LED8") (pin "3") (pinfunction "GND_3") (pintype "passive"))
      (node (ref "LED80") (pin "3") (pinfunction "GND_3") (pintype "passive"))
      (node (ref "LED81") (pin "3") (pinfunction "GND_3") (pintype "passive"))
      (node (ref "LED82") (pin "3") (pinfunction "GND_3") (pintype "passive"))
      (node (ref "LED83") (pin "3") (pinfunction "GND_3") (pintype "passive"))
      (node (ref "LED84") (pin "3") (pinfunction "GND_3") (pintype "passive"))
      (node (ref "LED85") (pin "3") (pinfunction "GND_3") (pintype "passive"))
      (node (ref "LED86") (pin "3") (pinfunction "GND_3") (pintype "passive"))
      (node (ref "LED87") (pin "3") (pinfunction "GND_3") (pintype "passive"))
      (node (ref "LED88") (pin "3") (pinfunction "GND_3") (pintype "passive"))
      (node (ref "LED89") (pin "3") (pinfunction "GND_3") (pintype "passive"))
      (node (ref "LED9") (pin "3") (pinfunction "GND_3") (pintype "passive"))
      (node (ref "LED90") (pin "3") (pinfunction "GND_3") (pintype "passive"))
      (node (ref "LED91") (pin "3") (pinfunction "GND_3") (pintype "passive"))
      (node (ref "LED92") (pin "3") (pinfunction "GND_3") (pintype "passive"))
      (node (ref "LED93") (pin "3") (pinfunction "GND_3") (pintype "passive"))
      (node (ref "LED94") (pin "3") (pinfunction "GND_3") (pintype "passive"))
      (node (ref "LED95") (pin "3") (pinfunction "GND_3") (pintype "passive"))
      (node (ref "LED96") (pin "3") (pinfunction "GND_3") (pintype "passive"))
      (node (ref "LED97") (pin "3") (pinfunction "GND_3") (pintype "passive"))
      (node (ref "LED98") (pin "3") (pinfunction "GND_3") (pintype "passive"))
      (node (ref "LED99") (pin "3") (pinfunction "GND_3") (pintype "passive"))
    )
    (net (code "4") (name "Net-(LED1-DOUT)") (class "Default")
      (node (ref "LED1") (pin "1") (pinfunction "DOUT_1") (pintype "passive"))
      (node (ref "LED2") (pin "4") (pinfunction "DIN_4") (pintype "passive"))
    )
    (net (code "5") (name "Net-(LED2-DOUT)") (class "Default")
      (node (ref "LED2") (pin "1") (pinfunction "DOUT_1") (pintype "passive"))
      (node (ref "LED3") (pin "4") (pinfunction "DIN_4") (pintype "passive"))
    )
    (net (code "6") (name "Net-(LED3-DOUT)") (class "Default")
      (node (ref "LED3") (pin "1") (pinfunction "DOUT_1") (pintype "passive"))
      (node (ref "LED4") (pin "4") (pinfunction "DIN_4") (pintype "passive"))
    )
    (net (code "7") (name "Net-(LED4-DOUT)") (class "Default")
      (node (ref "LED4") (pin "1") (pinfunction "DOUT_1") (pintype "passive"))
      (node (ref "LED5") (pin "4") (pinfunction "DIN_4") (pintype "passive"))
    )
    (net (code "8") (name "Net-(LED5-DOUT)") (class "Default")
      (node (ref "LED5") (pin "1") (pinfunction "DOUT_1") (pintype "passive"))
      (node (ref "LED6") (pin "4") (pinfunction "DIN_4") (pintype "passive"))
    )
    (net (code "9") (name "Net-(LED6-DOUT)") (class "Default")
      (node (ref "LED6") (pin "1") (pinfunction "DOUT_1") (pintype "passive"))
      (node (ref "LED7") (pin "4") (pinfunction "DIN_4") (pintype "passive"))
    )
    (net (code "10") (name "Net-(LED7-DOUT)") (class "Default")
      (node (ref "LED7") (pin "1") (pinfunction "DOUT_1") (pintype "passive"))
      (node (ref "LED8") (pin "4") (pinfunction "DIN_4") (pintype "passive"))
    )
    (net (code "11") (name "Net-(LED8-DOUT)") (class "Default")
      (node (ref "LED8") (pin "1") (pinfunction "DOUT_1") (pintype "passive"))
      (node (ref "LED9") (pin "4") (pinfunction "DIN_4") (pintype "passive"))
    )
    (net (code "12") (name "Net-(LED10-DIN)") (class "Default")
      (node (ref "LED10") (pin "4") (pinfunction "DIN_4") (pintype "passive"))
      (node (ref "LED9") (pin "1") (pinfunction "DOUT_1") (pintype "passive"))
    )
    (net (code "13") (name "Net-(LED10-DOUT)") (class "Default")
      (node (ref "LED10") (pin "1") (pinfunction "DOUT_1") (pintype "passive"))
      (node (ref "LED11") (pin "4") (pinfunction "DIN_4") (pintype "passive"))
    )
    (net (code "14") (name "Net-(LED11-DOUT)") (class "Default")
      (node (ref "LED11") (pin "1") (pinfunction "DOUT_1") (pintype "passive"))
      (node (ref "LED12") (pin "4") (pinfunction "DIN_4") (pintype "passive"))
    )
    (net (code "15") (name "Net-(LED12-DOUT)") (class "Default")
      (node (ref "LED12") (pin "1") (pinfunction "DOUT_1") (pintype "passive"))
      (node (ref "LED13") (pin "4") (pinfunction "DIN_4") (pintype "passive"))
    )
    (net (code "16") (name "Net-(LED13-DOUT)") (class "Default")
      (node (ref "LED13") (pin "1") (pinfunction "DOUT_1") (pintype "passive"))
      (node (ref "LED14") (pin "4") (pinfunction "DIN_4") (pintype "passive"))
    )
    (net (code "17") (name "Net-(LED14-DOUT)") (class "Default")
      (node (ref "LED14") (pin "1") (pinfunction "DOUT_1") (pintype "passive"))
      (node (ref "LED15") (pin "4") (pinfunction "DIN_4") (pintype "passive"))
    )
    (net (code "18") (name "Net-(LED15-DOUT)") (class "Default")
      (node (ref "LED15") (pin "1") (pinfunction "DOUT_1") (pintype "passive"))
      (node (ref "LED16") (pin "4") (pinfunction "DIN_4") (pintype "passive"))
    )
    (net (code "19") (name "Net-(LED16-DOUT)") (class "Default")
      (node (ref "LED16") (pin "1") (pinfunction "DOUT_1") (pintype "passive"))
      (node (ref "LED17") (pin "4") (pinfunction "DIN_4") (pintype "passive"))
    )
    (net (code "20") (name "Net-(LED17-DOUT)") (class "Default")
      (node (ref "LED17") (pin "1") (pinfunction "DOUT_1") (pintype "passive"))
      (node (ref "LED18") (pin "4") (pinfunction "DIN_4") (pintype "passive"))
    )
    (net (code "21") (name "Net-(LED18-DOUT)") (class "Default")
      (node (ref "LED18") (pin "1") (pinfunction "DOUT_1") (pintype "passive"))
      (node (ref "LED19") (pin "4") (pinfunction "DIN_4") (pintype "passive"))
    )
    (net (code "22") (name "Net-(LED19-DOUT)") (class "Default")
      (node (ref "LED19") (pin "1") (pinfunction "DOUT_1") (pintype "passive"))
      (node (ref "LED20") (pin "4") (pinfunction "DIN_4") (pintype "passive"))
    )
    (net (code "23") (name "Net-(LED20-DOUT)") (class "Default")
      (node (ref "LED20") (pin "1") (pinfunction "DOUT_1") (pintype "passive"))
      (node (ref "LED21") (pin "4") (pinfunction "DIN_4") (pintype "passive"))
    )
    (net (code "24") (name "Net-(LED21-DOUT)") (class "Default")
      (node (ref "LED21") (pin "1") (pinfunction "DOUT_1") (pintype "passive"))
      (node (ref "LED22") (pin "4") (pinfunction "DIN_4") (pintype "passive"))
    )
    (net (code "25") (name "Net-(LED22-DOUT)") (class "Default")
      (node (ref "LED22") (pin "1") (pinfunction "DOUT_1") (pintype "passive"))
      (node (ref "LED23") (pin "4") (pinfunction "DIN_4") (pintype "passive"))
    )
    (net (code "26") (name "Net-(LED23-DOUT)") (class "Default")
      (node (ref "LED23") (pin "1") (pinfunction "DOUT_1") (pintype "passive"))
      (node (ref "LED24") (pin "4") (pinfunction "DIN_4") (pintype "passive"))
    )
    (net (code "27") (name "Net-(LED24-DOUT)") (class "Default")
      (node (ref "LED24") (pin "1") (pinfunction "DOUT_1") (pintype "passive"))
      (node (ref "LED25") (pin "4") (pinfunction "DIN_4") (pintype "passive"))
    )
    (net (code "28") (name "Net-(LED25-DOUT)") (class "Default")
      (node (ref "LED25") (pin "1") (pinfunction "DOUT_1") (pintype "passive"))
      (node (ref "LED26") (pin "4") (pinfunction "DIN_4") (pintype "passive"))
    )
    (net (code "29") (name "Net-(LED26-DOUT)") (class "Default")
      (node (ref "LED26") (pin "1") (pinfunction "DOUT_1") (pintype "passive"))
      (node (ref "LED27") (pin "4") (pinfunction "DIN_4") (pintype "passive"))
    )
    (net (code "30") (name "Net-(LED27-DOUT)") (class "Default")
      (node (ref "LED27") (pin "1") (pinfunction "DOUT_1") (pintype "passive"))
      (node (ref "LED28") (pin "4") (pinfunction "DIN_4") (pintype "passive"))
    )
    (net (code "31") (name "Net-(LED28-DOUT)") (class "Default")
      (node (ref "LED28") (pin "1") (pinfunction "DOUT_1") (pintype "passive"))
      (node (ref "LED29") (pin "4") (pinfunction "DIN_4") (pintype "passive"))
    )
    (net (code "32") (name "Net-(LED29-DOUT)") (class "Default")
      (node (ref "LED29") (pin "1") (pinfunction "DOUT_1") (pintype "passive"))
      (node (ref "LED30") (pin "4") (pinfunction "DIN_4") (pintype "passive"))
    )
    (net (code "33") (name "Net-(LED30-DOUT)") (class "Default")
      (node (ref "LED30") (pin "1") (pinfunction "DOUT_1") (pintype "passive"))
      (node (ref "LED31") (pin "4") (pinfunction "DIN_4") (pintype "passive"))
    )
    (net (code "34") (name "Net-(LED31-DOUT)") (class "Default")
      (node (ref "LED31") (pin "1") (pinfunction "DOUT_1") (pintype "passive"))
      (node (ref "LED32") (pin "4") (pinfunction "DIN_4") (pintype "passive"))
    )
    (net (code "35") (name "Net-(LED32-DOUT)") (class "Default")
      (node (ref "LED32") (pin "1") (pinfunction "DOUT_1") (pintype "passive"))
      (node (ref "LED33") (pin "4") (pinfunction "DIN_4") (pintype "passive"))
    )
    (net (code "36") (name "Net-(LED33-DOUT)") (class "Default")
      (node (ref "LED33") (pin "1") (pinfunction "DOUT_1") (pintype "passive"))
      (node (ref "LED34") (pin "4") (pinfunction "DIN_4") (pintype "passive"))
    )
    (net (code "37") (name "Net-(LED34-DOUT)") (class "Default")
      (node (ref "LED34") (pin "1") (pinfunction "DOUT_1") (pintype "passive"))
      (node (ref "LED35") (pin "4") (pinfunction "DIN_4") (pintype "passive"))
    )
    (net (code "38") (name "Net-(LED35-DOUT)") (class "Default")
      (node (ref "LED35") (pin "1") (pinfunction "DOUT_1") (pintype "passive"))
      (node (ref "LED36") (pin "4") (pinfunction "DIN_4") (pintype "passive"))
    )
    (net (code "39") (name "Net-(LED36-DOUT)") (class "Default")
      (node (ref "LED36") (pin "1") (pinfunction "DOUT_1") (pintype "passive"))
      (node (ref "LED37") (pin "4") (pinfunction "DIN_4") (pintype "passive"))
    )
    (net (code "40") (name "Net-(LED37-DOUT)") (class "Default")
      (node (ref "LED37") (pin "1") (pinfunction "DOUT_1") (pintype "passive"))
      (node (ref "LED38") (pin "4") (pinfunction "DIN_4") (pintype "passive"))
    )
    (net (code "41") (name "Net-(LED38-DOUT)") (class "Default")
      (node (ref "LED38") (pin "1") (pinfunction "DOUT_1") (pintype "passive"))
      (node (ref "LED39") (pin "4") (pinfunction "DIN_4") (pintype "passive"))
    )
    (net (code "42") (name "Net-(LED39-DOUT)") (class "Default")
      (node (ref "LED39") (pin "1") (pinfunction "DOUT_1") (pintype "passive"))
      (node (ref "LED40") (pin "4") (pinfunction "DIN_4") (pintype "passive"))
    )
    (net (code "43") (name "Net-(LED40-DOUT)") (class "Default")
      (node (ref "LED40") (pin "1") (pinfunction "DOUT_1") (pintype "passive"))
      (node (ref "LED41") (pin "4") (pinfunction "DIN_4") (pintype "passive"))
    )
    (net (code "44") (name "Net-(LED41-DOUT)") (class "Default")
      (node (ref "LED41") (pin "1") (pinfunction "DOUT_1") (pintype "passive"))
      (node (ref "LED42") (pin "4") (pinfunction "DIN_4") (pintype "passive"))
    )
    (net (code "45") (name "Net-(LED42-DOUT)") (class "Default")
      (node (ref "LED42") (pin "1") (pinfunction "DOUT_1") (pintype "passive"))
      (node (ref "LED43") (pin "4") (pinfunction "DIN_4") (pintype "passive"))
    )
    (net (code "46") (name "Net-(LED43-DOUT)") (class "Default")
      (node (ref "LED43") (pin "1") (pinfunction "DOUT_1") (pintype "passive"))
      (node (ref "LED44") (pin "4") (pinfunction "DIN_4") (pintype "passive"))
    )
    (net (code "47") (name "Net-(LED44-DOUT)") (class "Default")
      (node (ref "LED44") (pin "1") (pinfunction "DOUT_1") (pintype "passive"))
      (node (ref "LED45") (pin "4") (pinfunction "DIN_4") (pintype "passive"))
    )
    (net (code "48") (name "Net-(LED45-DOUT)") (class "Default")
      (node (ref "LED45") (pin "1") (pinfunction "DOUT_1") (pintype "passive"))
      (node (ref "LED46") (pin "4") (pinfunction "DIN_4") (pintype "passive"))
    )
    (net (code "49") (name "Net-(LED46-DOUT)") (class "Default")
      (node (ref "LED46") (pin "1") (pinfunction "DOUT_1") (pintype "passive"))
      (node (ref "LED47") (pin "4") (pinfunction "DIN_4") (pintype "passive"))
    )
    (net (code "50") (name "Net-(LED47-DOUT)") (class "Default")
      (node (ref "LED47") (pin "1") (pinfunction "DOUT_1") (pintype "passive"))
      (node (ref "LED48") (pin "4") (pinfunction "DIN_4") (pintype "passive"))
    )
    (net (code "51") (name "Net-(LED48-DOUT)") (class "Default")
      (node (ref "LED48") (pin "1") (pinfunction "DOUT_1") (pintype "passive"))
      (node (ref "LED49") (pin "4") (pinfunction "DIN_4") (pintype "passive"))
    )
    (net (code "52") (name "Net-(LED49-DOUT)") (class "Default")
      (node (ref "LED49") (pin "1") (pinfunction "DOUT_1") (pintype "passive"))
      (node (ref "LED50") (pin "4") (pinfunction "DIN_4") (pintype "passive"))
    )
    (net (code "53") (name "Net-(LED50-DOUT)") (class "Default")
      (node (ref "LED50") (pin "1") (pinfunction "DOUT_1") (pintype "passive"))
      (node (ref "LED51") (pin "4") (pinfunction "DIN_4") (pintype "passive"))
    )
    (net (code "54") (name "Net-(LED51-DOUT)") (class "Default")
      (node (ref "LED51") (pin "1") (pinfunction "DOUT_1") (pintype "passive"))
      (node (ref "LED52") (pin "4") (pinfunction "DIN_4") (pintype "passive"))
    )
    (net (code "55") (name "Net-(LED52-DOUT)") (class "Default")
      (node (ref "LED52") (pin "1") (pinfunction "DOUT_1") (pintype "passive"))
      (node (ref "LED53") (pin "4") (pinfunction "DIN_4") (pintype "passive"))
    )
    (net (code "56") (name "Net-(LED53-DOUT)") (class "Default")
      (node (ref "LED53") (pin "1") (pinfunction "DOUT_1") (pintype "passive"))
      (node (ref "LED54") (pin "4") (pinfunction "DIN_4") (pintype "passive"))
    )
    (net (code "57") (name "Net-(LED54-DOUT)") (class "Default")
      (node (ref "LED54") (pin "1") (pinfunction "DOUT_1") (pintype "passive"))
      (node (ref "LED55") (pin "4") (pinfunction "DIN_4") (pintype "passive"))
    )
    (net (code "58") (name "Net-(LED55-DOUT)") (class "Default")
      (node (ref "LED55") (pin "1") (pinfunction "DOUT_1") (pintype "passive"))
      (node (ref "LED56") (pin "4") (pinfunction "DIN_4") (pintype "passive"))
    )
    (net (code "59") (name "Net-(LED56-DOUT)") (class "Default")
      (node (ref "LED56") (pin "1") (pinfunction "DOUT_1") (pintype "passive"))
      (node (ref "LED57") (pin "4") (pinfunction "DIN_4") (pintype "passive"))
    )
    (net (code "60") (name "Net-(LED57-DOUT)") (class "Default")
      (node (ref "LED57") (pin "1") (pinfunction "DOUT_1") (pintype "passive"))
      (node (ref "LED58") (pin "4") (pinfunction "DIN_4") (pintype "passive"))
    )
    (net (code "61") (name "Net-(LED58-DOUT)") (class "Default")
      (node (ref "LED58") (pin "1") (pinfunction "DOUT_1") (pintype "passive"))
      (node (ref "LED59") (pin "4") (pinfunction "DIN_4") (pintype "passive"))
    )
    (net (code "62") (name "Net-(LED59-DOUT)") (class "Default")
      (node (ref "LED59") (pin "1") (pinfunction "DOUT_1") (pintype "passive"))
      (node (ref "LED60") (pin "4") (pinfunction "DIN_4") (pintype "passive"))
    )
    (net (code "63") (name "Net-(LED60-DOUT)") (class "Default")
      (node (ref "LED60") (pin "1") (pinfunction "DOUT_1") (pintype "passive"))
      (node (ref "LED61") (pin "4") (pinfunction "DIN_4") (pintype "passive"))
    )
    (net (code "64") (name "Net-(LED61-DOUT)") (class "Default")
      (node (ref "LED61") (pin "1") (pinfunction "DOUT_1") (pintype "passive"))
      (node (ref "LED62") (pin "4") (pinfunction "DIN_4") (pintype "passive"))
    )
    (net (code "65") (name "Net-(LED62-DOUT)") (class "Default")
      (node (ref "LED62") (pin "1") (pinfunction "DOUT_1") (pintype "passive"))
      (node (ref "LED63") (pin "4") (pinfunction "DIN_4") (pintype "passive"))
    )
    (net (code "66") (name "Net-(LED63-DOUT)") (class "Default")
      (node (ref "LED63") (pin "1") (pinfunction "DOUT_1") (pintype "passive"))
      (node (ref "LED64") (pin "4") (pinfunction "DIN_4") (pintype "passive"))
    )
    (net (code "67") (name "Net-(LED64-DOUT)") (class "Default")
      (node (ref "LED64") (pin "1") (pinfunction "DOUT_1") (pintype "passive"))
      (node (ref "LED65") (pin "4") (pinfunction "DIN_4") (pintype "passive"))
    )
    (net (code "68") (name "Net-(LED65-DOUT)") (class "Default")
      (node (ref "LED65") (pin "1") (pinfunction "DOUT_1") (pintype "passive"))
      (node (ref "LED66") (pin "4") (pinfunction "DIN_4") (pintype "passive"))
    )
    (net (code "69") (name "Net-(LED66-DOUT)") (class "Default")
      (node (ref "LED66") (pin "1") (pinfunction "DOUT_1") (pintype "passive"))
      (node (ref "LED67") (pin "4") (pinfunction "DIN_4") (pintype "passive"))
    )
    (net (code "70") (name "Net-(LED67-DOUT)") (class "Default")
      (node (ref "LED67") (pin "1") (pinfunction "DOUT_1") (pintype "passive"))
      (node (ref "LED68") (pin "4") (pinfunction "DIN_4") (pintype "passive"))
    )
    (net (code "71") (name "Net-(LED68-DOUT)") (class "Default")
      (node (ref "LED68") (pin "1") (pinfunction "DOUT_1") (pintype "passive"))
      (node (ref "LED69") (pin "4") (pinfunction "DIN_4") (pintype "passive"))
    )
    (net (code "72") (name "Net-(LED69-DOUT)") (class "Default")
      (node (ref "LED69") (pin "1") (pinfunction "DOUT_1") (pintype "passive"))
      (node (ref "LED70") (pin "4") (pinfunction "DIN_4") (pintype "passive"))
    )
    (net (code "73") (name "Net-(LED70-DOUT)") (class "Default")
      (node (ref "LED70") (pin "1") (pinfunction "DOUT_1") (pintype "passive"))
      (node (ref "LED71") (pin "4") (pinfunction "DIN_4") (pintype "passive"))
    )
    (net (code "74") (name "Net-(LED71-DOUT)") (class "Default")
      (node (ref "LED71") (pin "1") (pinfunction "DOUT_1") (pintype "passive"))
      (node (ref "LED72") (pin "4") (pinfunction "DIN_4") (pintype "passive"))
    )
    (net (code "75") (name "Net-(LED72-DOUT)") (class "Default")
      (node (ref "LED72") (pin "1") (pinfunction "DOUT_1") (pintype "passive"))
      (node (ref "LED73") (pin "4") (pinfunction "DIN_4") (pintype "passive"))
    )
    (net (code "76") (name "Net-(LED73-DOUT)") (class "Default")
      (node (ref "LED73") (pin "1") (pinfunction "DOUT_1") (pintype "passive"))
      (node (ref "LED74") (pin "4") (pinfunction "DIN_4") (pintype "passive"))
    )
    (net (code "77") (name "Net-(LED74-DOUT)") (class "Default")
      (node (ref "LED74") (pin "1") (pinfunction "DOUT_1") (pintype "passive"))
      (node (ref "LED75") (pin "4") (pinfunction "DIN_4") (pintype "passive"))
    )
    (net (code "78") (name "Net-(LED75-DOUT)") (class "Default")
      (node (ref "LED75") (pin "1") (pinfunction "DOUT_1") (pintype "passive"))
      (node (ref "LED76") (pin "4") (pinfunction "DIN_4") (pintype "passive"))
    )
    (net (code "79") (name "Net-(LED76-DOUT)") (class "Default")
      (node (ref "LED76") (pin "1") (pinfunction "DOUT_1") (pintype "passive"))
      (node (ref "LED77") (pin "4") (pinfunction "DIN_4") (pintype "passive"))
    )
    (net (code "80") (name "Net-(LED77-DOUT)") (class "Default")
      (node (ref "LED77") (pin "1") (pinfunction "DOUT_1") (pintype "passive"))
      (node (ref "LED78") (pin "4") (pinfunction "DIN_4") (pintype "passive"))
    )
    (net (code "81") (name "Net-(LED78-DOUT)") (class "Default")
      (node (ref "LED78") (pin "1") (pinfunction "DOUT_1") (pintype "passive"))
      (node (ref "LED79") (pin "4") (pinfunction "DIN_4") (pintype "passive"))
    )
    (net (code "82") (name "Net-(LED79-DOUT)") (class "Default")
      (node (ref "LED79") (pin "1") (pinfunction "DOUT_1") (pintype "passive"))
      (node (ref "LED80") (pin "4") (pinfunction "DIN_4") (pintype "passive"))
    )
    (net (code "83") (name "Net-(LED80-DOUT)") (class "Default")
      (node (ref "LED80") (pin "1") (pinfunction "DOUT_1") (pintype "passive"))
      (node (ref "LED81") (pin "4") (pinfunction "DIN_4") (pintype "passive"))
    )
    (net (code "84") (name "Net-(LED81-DOUT)") (class "Default")
      (node (ref "LED81") (pin "1") (pinfunction "DOUT_1") (pintype "passive"))
      (node (ref "LED82") (pin "4") (pinfunction "DIN_4") (pintype "passive"))
    )
    (net (code "85") (name "Net-(LED83-DOUT)") (class "Default")
      (node (ref "LED83") (pin "1") (pinfunction "DOUT_1") (pintype "passive"))
      (node (ref "LED84") (pin "4") (pinfunction "DIN_4") (pintype "passive"))
    )
    (net (code "86") (name "Net-(LED84-DOUT)") (class "Default")
      (node (ref "LED84") (pin "1") (pinfunction "DOUT_1") (pintype "passive"))
      (node (ref "LED85") (pin "4") (pinfunction "DIN_4") (pintype "passive"))
    )
    (net (code "87") (name "Net-(LED85-DOUT)") (class "Default")
      (node (ref "LED85") (pin "1") (pinfunction "DOUT_1") (pintype "passive"))
      (node (ref "LED86") (pin "4") (pinfunction "DIN_4") (pintype "passive"))
    )
    (net (code "88") (name "Net-(LED86-DOUT)") (class "Default")
      (node (ref "LED86") (pin "1") (pinfunction "DOUT_1") (pintype "passive"))
      (node (ref "LED87") (pin "4") (pinfunction "DIN_4") (pintype "passive"))
    )
    (net (code "89") (name "Net-(LED87-DOUT)") (class "Default")
      (node (ref "LED87") (pin "1") (pinfunction "DOUT_1") (pintype "passive"))
      (node (ref "LED88") (pin "4") (pinfunction "DIN_4") (pintype "passive"))
    )
    (net (code "90") (name "Net-(LED88-DOUT)") (class "Default")
      (node (ref "LED88") (pin "1") (pinfunction "DOUT_1") (pintype "passive"))
      (node (ref "LED89") (pin "4") (pinfunction "DIN_4") (pintype "passive"))
    )
    (net (code "91") (name "Net-(LED89-DOUT)") (class "Default")
      (node (ref "LED89") (pin "1") (pinfunction "DOUT_1") (pintype "passive"))
      (node (ref "LED90") (pin "4") (pinfunction "DIN_4") (pintype "passive"))
    )
    (net (code "92") (name "Net-(LED90-DOUT)") (class "Default")
      (node (ref "LED90") (pin "1") (pinfunction "DOUT_1") (pintype "passive"))
      (node (ref "LED91") (pin "4") (pinfunction "DIN_4") (pintype "passive"))
    )
    (net (code "93") (name "Net-(LED91-DOUT)") (class "Default")
      (node (ref "LED91") (pin "1") (pinfunction "DOUT_1") (pintype "passive"))
      (node (ref "LED92") (pin "4") (pinfunction "DIN_4") (pintype "passive"))
    )
    (net (code "94") (name "Net-(LED92-DOUT)") (class "Default")
      (node (ref "LED92") (pin "1") (pinfunction "DOUT_1") (pintype "passive"))
      (node (ref "LED93") (pin "4") (pinfunction "DIN_4") (pintype "passive"))
    )
    (net (code "95") (name "Net-(LED93-DOUT)") (class "Default")
      (node (ref "LED93") (pin "1") (pinfunction "DOUT_1") (pintype "passive"))
      (node (ref "LED94") (pin "4") (pinfunction "DIN_4") (pintype "passive"))
    )
    (net (code "96") (name "Net-(LED94-DOUT)") (class "Default")
      (node (ref "LED94") (pin "1") (pinfunction "DOUT_1") (pintype "passive"))
      (node (ref "LED95") (pin "4") (pinfunction "DIN_4") (pintype "passive"))
    )
    (net (code "97") (name "Net-(LED95-DOUT)") (class "Default")
      (node (ref "LED95") (pin "1") (pinfunction "DOUT_1") (pintype "passive"))
      (node (ref "LED96") (pin "4") (pinfunction "DIN_4") (pintype "passive"))
    )
    (net (code "98") (name "Net-(LED96-DOUT)") (class "Default")
      (node (ref "LED96") (pin "1") (pinfunction "DOUT_1") (pintype "passive"))
      (node (ref "LED97") (pin "4") (pinfunction "DIN_4") (pintype "passive"))
    )
    (net (code "99") (name "Net-(LED97-DOUT)") (class "Default")
      (node (ref "LED97") (pin "1") (pinfunction "DOUT_1") (pintype "passive"))
      (node (ref "LED98") (pin "4") (pinfunction "DIN_4") (pintype "passive"))
    )
    (net (code "100") (name "Net-(LED98-DOUT)") (class "Default")
      (node (ref "LED98") (pin "1") (pinfunction "DOUT_1") (pintype "passive"))
      (node (ref "LED99") (pin "4") (pinfunction "DIN_4") (pintype "passive"))
    )
    (net (code "101") (name "Net-(LED100-DIN)") (class "Default")
      (node (ref "LED100") (pin "4") (pinfunction "DIN_4") (pintype "passive"))
      (node (ref "LED99") (pin "1") (pinfunction "DOUT_1") (pintype "passive"))
    )
    (net (code "102") (name "Net-(LED100-DOUT)") (class "Default")
      (node (ref "LED100") (pin "1") (pinfunction "DOUT_1") (pintype "passive"))
      (node (ref "LED101") (pin "4") (pinfunction "DIN_4") (pintype "passive"))
    )
    (net (code "103") (name "Net-(LED101-DOUT)") (class "Default")
      (node (ref "LED101") (pin "1") (pinfunction "DOUT_1") (pintype "passive"))
      (node (ref "LED102") (pin "4") (pinfunction "DIN_4") (pintype "passive"))
    )
    (net (code "104") (name "Net-(LED102-DOUT)") (class "Default")
      (node (ref "LED102") (pin "1") (pinfunction "DOUT_1") (pintype "passive"))
      (node (ref "LED103") (pin "4") (pinfunction "DIN_4") (pintype "passive"))
    )
    (net (code "105") (name "Net-(LED103-DOUT)") (class "Default")
      (node (ref "LED103") (pin "1") (pinfunction "DOUT_1") (pintype "passive"))
      (node (ref "LED104") (pin "4") (pinfunction "DIN_4") (pintype "passive"))
    )
    (net (code "106") (name "Net-(LED104-DOUT)") (class "Default")
      (node (ref "LED104") (pin "1") (pinfunction "DOUT_1") (pintype "passive"))
      (node (ref "LED105") (pin "4") (pinfunction "DIN_4") (pintype "passive"))
    )
    (net (code "107") (name "Net-(LED105-DOUT)") (class "Default")
      (node (ref "LED105") (pin "1") (pinfunction "DOUT_1") (pintype "passive"))
      (node (ref "LED106") (pin "4") (pinfunction "DIN_4") (pintype "passive"))
    )
    (net (code "108") (name "Net-(LED106-DOUT)") (class "Default")
      (node (ref "LED106") (pin "1") (pinfunction "DOUT_1") (pintype "passive"))
      (node (ref "LED107") (pin "4") (pinfunction "DIN_4") (pintype "passive"))
    )
    (net (code "109") (name "Net-(LED107-DOUT)") (class "Default")
      (node (ref "LED107") (pin "1") (pinfunction "DOUT_1") (pintype "passive"))
      (node (ref "LED108") (pin "4") (pinfunction "DIN_4") (pintype "passive"))
    )
    (net (code "110") (name "VCC") (class "Default")
      (node (ref "LED1") (pin "2") (pinfunction "VDD_2") (pintype "passive"))
      (node (ref "LED10") (pin "2") (pinfunction "VDD_2") (pintype "passive"))
      (node (ref "LED100") (pin "2") (pinfunction "VDD_2") (pintype "passive"))
      (node (ref "LED101") (pin "2") (pinfunction "VDD_2") (pintype "passive"))
      (node (ref "LED102") (pin "2") (pinfunction "VDD_2") (pintype "passive"))
      (node (ref "LED103") (pin "2") (pinfunction "VDD_2") (pintype "passive"))
      (node (ref "LED104") (pin "2") (pinfunction "VDD_2") (pintype "passive"))
      (node (ref "LED105") (pin "2") (pinfunction "VDD_2") (pintype "passive"))
      (node (ref "LED106") (pin "2") (pinfunction "VDD_2") (pintype "passive"))
      (node (ref "LED107") (pin "2") (pinfunction "VDD_2") (pintype "passive"))
      (node (ref "LED108") (pin "2") (pinfunction "VDD_2") (pintype "passive"))
      (node (ref "LED11") (pin "2") (pinfunction "VDD_2") (pintype "passive"))
      (node (ref "LED12") (pin "2") (pinfunction "VDD_2") (pintype "passive"))
      (node (ref "LED13") (pin "2") (pinfunction "VDD_2") (pintype "passive"))
      (node (ref "LED14") (pin "2") (pinfunction "VDD_2") (pintype "passive"))
      (node (ref "LED15") (pin "2") (pinfunction "VDD_2") (pintype "passive"))
      (node (ref "LED16") (pin "2") (pinfunction "VDD_2") (pintype "passive"))
      (node (ref "LED17") (pin "2") (pinfunction "VDD_2") (pintype "passive"))
      (node (ref "LED18") (pin "2") (pinfunction "VDD_2") (pintype "passive"))
      (node (ref "LED19") (pin "2") (pinfunction "VDD_2") (pintype "passive"))
      (node (ref "LED2") (pin "2") (pinfunction "VDD_2") (pintype "passive"))
      (node (ref "LED20") (pin "2") (pinfunction "VDD_2") (pintype "passive"))
      (node (ref "LED21") (pin "2") (pinfunction "VDD_2") (pintype "passive"))
      (node (ref "LED22") (pin "2") (pinfunction "VDD_2") (pintype "passive"))
      (node (ref "LED23") (pin "2") (pinfunction "VDD_2") (pintype "passive"))
      (node (ref "LED24") (pin "2") (pinfunction "VDD_2") (pintype "passive"))
      (node (ref "LED25") (pin "2") (pinfunction "VDD_2") (pintype "passive"))
      (node (ref "LED26") (pin "2") (pinfunction "VDD_2") (pintype "passive"))
      (node (ref "LED27") (pin "2") (pinfunction "VDD_2") (pintype "passive"))
      (node (ref "LED28") (pin "2") (pinfunction "VDD_2") (pintype "passive"))
      (node (ref "LED29") (pin "2") (pinfunction "VDD_2") (pintype "passive"))
      (node (ref "LED3") (pin "2") (pinfunction "VDD_2") (pintype "passive"))
      (node (ref "LED30") (pin "2") (pinfunction "VDD_2") (pintype "passive"))
      (node (ref "LED31") (pin "2") (pinfunction "VDD_2") (pintype "passive"))
      (node (ref "LED32") (pin "2") (pinfunction "VDD_2") (pintype "passive"))
      (node (ref "LED33") (pin "2") (pinfunction "VDD_2") (pintype "passive"))
      (node (ref "LED34") (pin "2") (pinfunction "VDD_2") (pintype "passive"))
      (node (ref "LED35") (pin "2") (pinfunction "VDD_2") (pintype "passive"))
      (node (ref "LED36") (pin "2") (pinfunction "VDD_2") (pintype "passive"))
      (node (ref "LED37") (pin "2") (pinfunction "VDD_2") (pintype "passive"))
      (node (ref "LED38") (pin "2") (pinfunction "VDD_2") (pintype "passive"))
      (node (ref "LED39") (pin "2") (pinfunction "VDD_2") (pintype "passive"))
      (node (ref "LED4") (pin "2") (pinfunction "VDD_2") (pintype "passive"))
      (node (ref "LED40") (pin "2") (pinfunction "VDD_2") (pintype "passive"))
      (node (ref "LED41") (pin "2") (pinfunction "VDD_2") (pintype "passive"))
      (node (ref "LED42") (pin "2") (pinfunction "VDD_2") (pintype "passive"))
      (node (ref "LED43") (pin "2") (pinfunction "VDD_2") (pintype "passive"))
      (node (ref "LED44") (pin "2") (pinfunction "VDD_2") (pintype "passive"))
      (node (ref "LED45") (pin "2") (pinfunction "VDD_2") (pintype "passive"))
      (node (ref "LED46") (pin "2") (pinfunction "VDD_2") (pintype "passive"))
      (node (ref "LED47") (pin "2") (pinfunction "VDD_2") (pintype "passive"))
      (node (ref "LED48") (pin "2") (pinfunction "VDD_2") (pintype "passive"))
      (node (ref "LED49") (pin "2") (pinfunction "VDD_2") (pintype "passive"))
      (node (ref "LED5") (pin "2") (pinfunction "VDD_2") (pintype "passive"))
      (node (ref "LED50") (pin "2") (pinfunction "VDD_2") (pintype "passive"))
      (node (ref "LED51") (pin "2") (pinfunction "VDD_2") (pintype "passive"))
      (node (ref "LED52") (pin "2") (pinfunction "VDD_2") (pintype "passive"))
      (node (ref "LED53") (pin "2") (pinfunction "VDD_2") (pintype "passive"))
      (node (ref "LED54") (pin "2") (pinfunction "VDD_2") (pintype "passive"))
      (node (ref "LED55") (pin "2") (pinfunction "VDD_2") (pintype "passive"))
      (node (ref "LED56") (pin "2") (pinfunction "VDD_2") (pintype "passive"))
      (node (ref "LED57") (pin "2") (pinfunction "VDD_2") (pintype "passive"))
      (node (ref "LED58") (pin "2") (pinfunction "VDD_2") (pintype "passive"))
      (node (ref "LED59") (pin "2") (pinfunction "VDD_2") (pintype "passive"))
      (node (ref "LED6") (pin "2") (pinfunction "VDD_2") (pintype "passive"))
      (node (ref "LED60") (pin "2") (pinfunction "VDD_2") (pintype "passive"))
      (node (ref "LED61") (pin "2") (pinfunction "VDD_2") (pintype "passive"))
      (node (ref "LED62") (pin "2") (pinfunction "VDD_2") (pintype "passive"))
      (node (ref "LED63") (pin "2") (pinfunction "VDD_2") (pintype "passive"))
      (node (ref "LED64") (pin "2") (pinfunction "VDD_2") (pintype "passive"))
      (node (ref "LED65") (pin "2") (pinfunction "VDD_2") (pintype "passive"))
      (node (ref "LED66") (pin "2") (pinfunction "VDD_2") (pintype "passive"))
      (node (ref "LED67") (pin "2") (pinfunction "VDD_2") (pintype "passive"))
      (node (ref "LED68") (pin "2") (pinfunction "VDD_2") (pintype "passive"))
      (node (ref "LED69") (pin "2") (pinfunction "VDD_2") (pintype "passive"))
      (node (ref "LED7") (pin "2") (pinfunction "VDD_2") (pintype "passive"))
      (node (ref "LED70") (pin "2") (pinfunction "VDD_2") (pintype "passive"))
      (node (ref "LED71") (pin "2") (pinfunction "VDD_2") (pintype "passive"))
      (node (ref "LED72") (pin "2") (pinfunction "VDD_2") (pintype "passive"))
      (node (ref "LED73") (pin "2") (pinfunction "VDD_2") (pintype "passive"))
      (node (ref "LED74") (pin "2") (pinfunction "VDD_2") (pintype "passive"))
      (node (ref "LED75") (pin "2") (pinfunction "VDD_2") (pintype "passive"))
      (node (ref "LED76") (pin "2") (pinfunction "VDD_2") (pintype "passive"))
      (node (ref "LED77") (pin "2") (pinfunction "VDD_2") (pintype "passive"))
      (node (ref "LED78") (pin "2") (pinfunction "VDD_2") (pintype "passive"))
      (node (ref "LED79") (pin "2") (pinfunction "VDD_2") (pintype "passive"))
      (node (ref "LED8") (pin "2") (pinfunction "VDD_2") (pintype "passive"))
      (node (ref "LED80") (pin "2") (pinfunction "VDD_2") (pintype "passive"))
      (node (ref "LED81") (pin "2") (pinfunction "VDD_2") (pintype "passive"))
      (node (ref "LED82") (pin "2") (pinfunction "VDD_2") (pintype "passive"))
      (node (ref "LED83") (pin "2") (pinfunction "VDD_2") (pintype "passive"))
      (node (ref "LED84") (pin "2") (pinfunction "VDD_2") (pintype "passive"))
      (node (ref "LED85") (pin "2") (pinfunction "VDD_2") (pintype "passive"))
      (node (ref "LED86") (pin "2") (pinfunction "VDD_2") (pintype "passive"))
      (node (ref "LED87") (pin "2") (pinfunction "VDD_2") (pintype "passive"))
      (node (ref "LED88") (pin "2") (pinfunction "VDD_2") (pintype "passive"))
      (node (ref "LED89") (pin "2") (pinfunction "VDD_2") (pintype "passive"))
      (node (ref "LED9") (pin "2") (pinfunction "VDD_2") (pintype "passive"))
      (node (ref "LED90") (pin "2") (pinfunction "VDD_2") (pintype "passive"))
      (node (ref "LED91") (pin "2") (pinfunction "VDD_2") (pintype "passive"))
      (node (ref "LED92") (pin "2") (pinfunction "VDD_2") (pintype "passive"))
      (node (ref "LED93") (pin "2") (pinfunction "VDD_2") (pintype "passive"))
      (node (ref "LED94") (pin "2") (pinfunction "VDD_2") (pintype "passive"))
      (node (ref "LED95") (pin "2") (pinfunction "VDD_2") (pintype "passive"))
      (node (ref "LED96") (pin "2") (pinfunction "VDD_2") (pintype "passive"))
      (node (ref "LED97") (pin "2") (pinfunction "VDD_2") (pintype "passive"))
      (node (ref "LED98") (pin "2") (pinfunction "VDD_2") (pintype "passive"))
      (node (ref "LED99") (pin "2") (pinfunction "VDD_2") (pintype "passive"))
    )
    (net (code "111") (name "unconnected-(LED82-DOUT-Pad1)") (class "Default")
      (node (ref "LED82") (pin "1") (pinfunction "DOUT_1") (pintype "passive+no_connect"))
    )
    (net (code "112") (name "unconnected-(LED108-DOUT-Pad1)") (class "Default")
      (node (ref "LED108") (pin "1") (pinfunction "DOUT_1") (pintype "passive+no_connect"))
    )
  )
)
